# Controller-Board_Rack-PDU_1_0.net
KiCad netlist of a schematic drawn in EAGLE
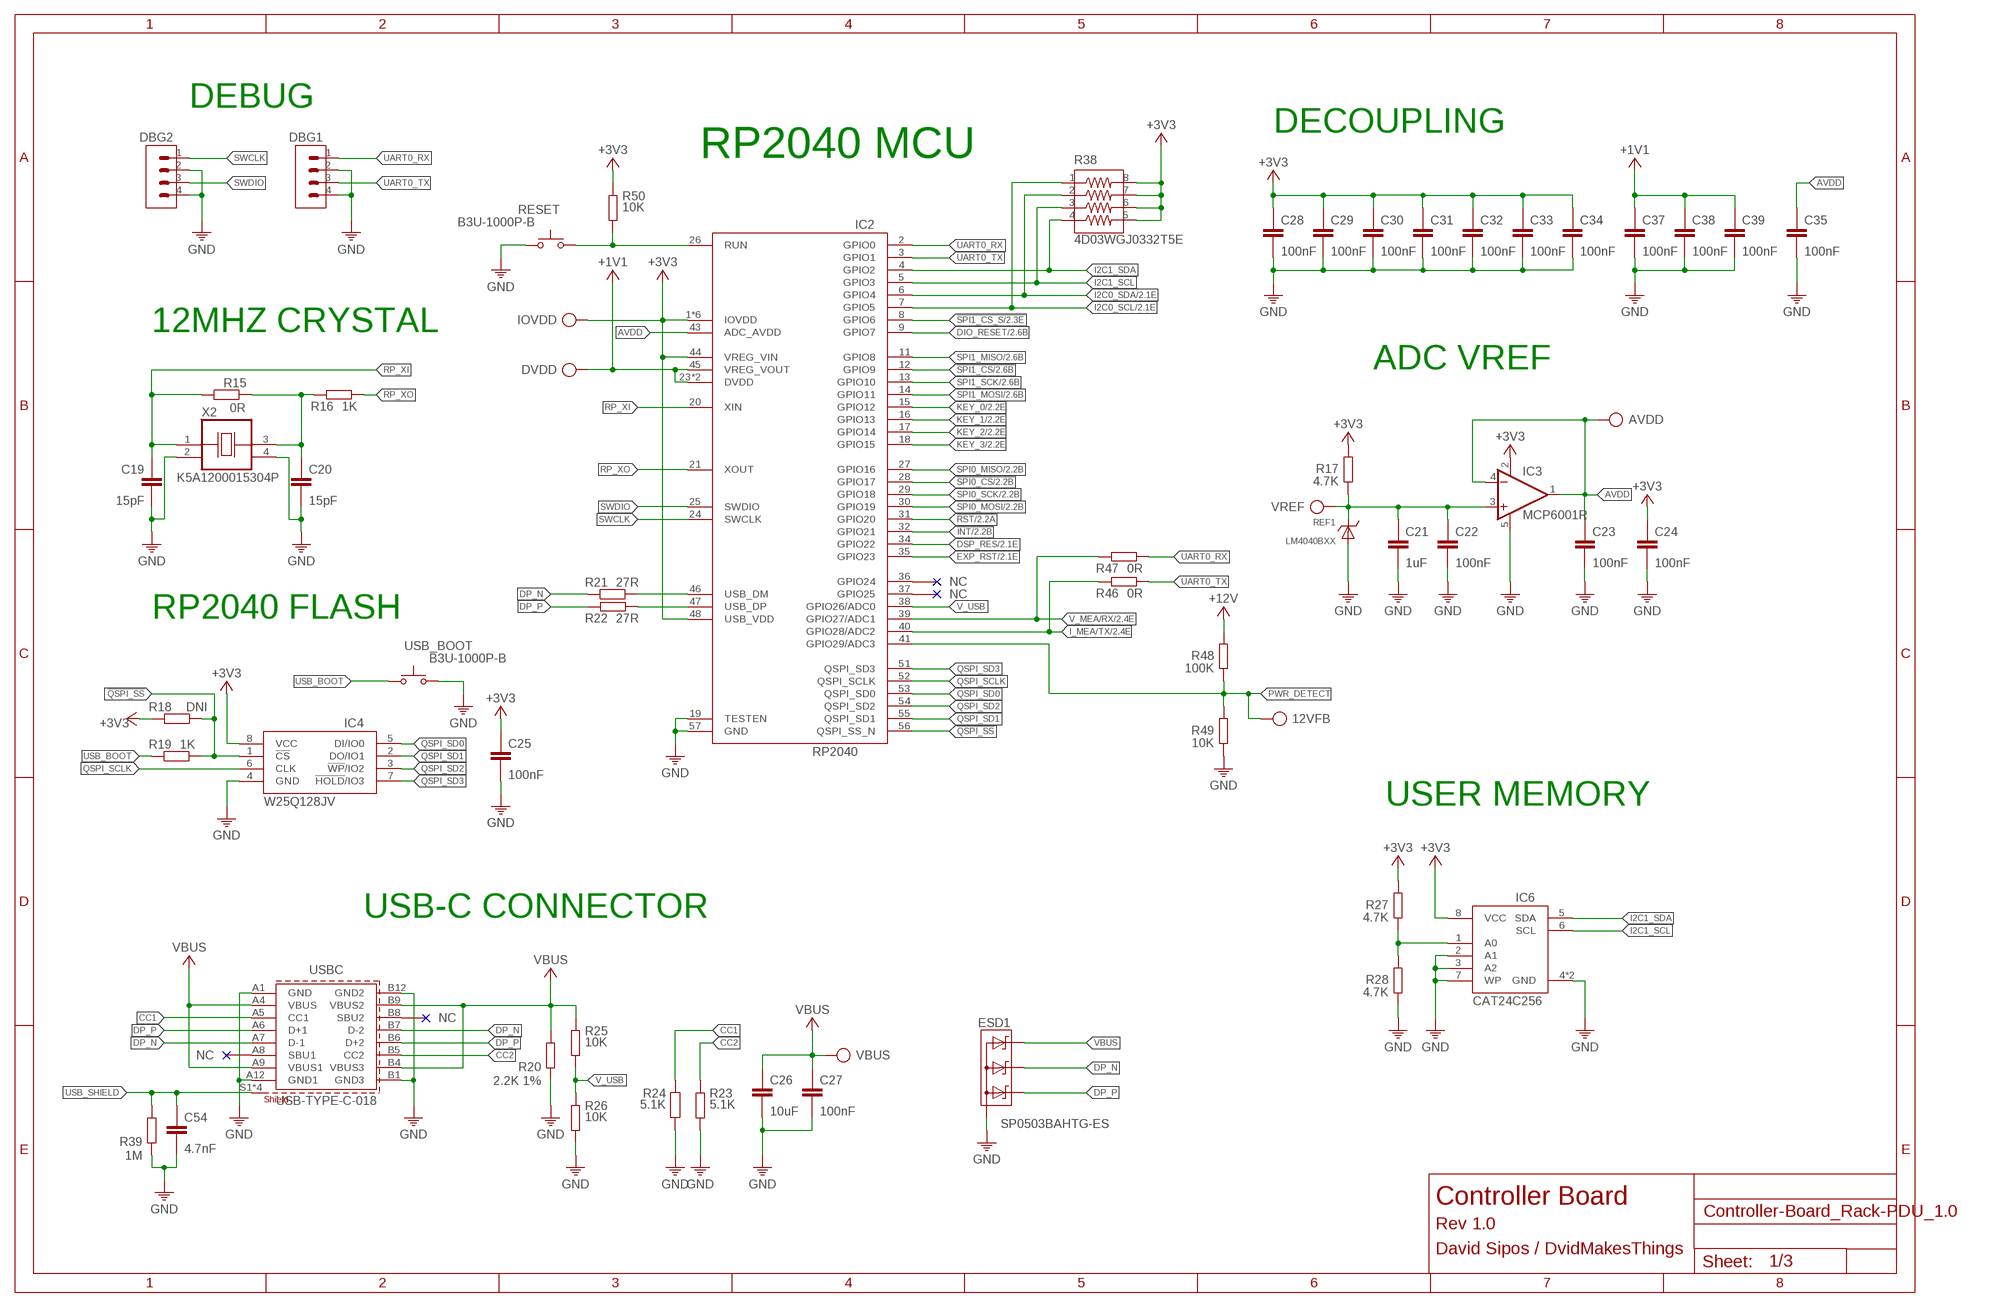
[diagram p0: schematic, sheet 1]
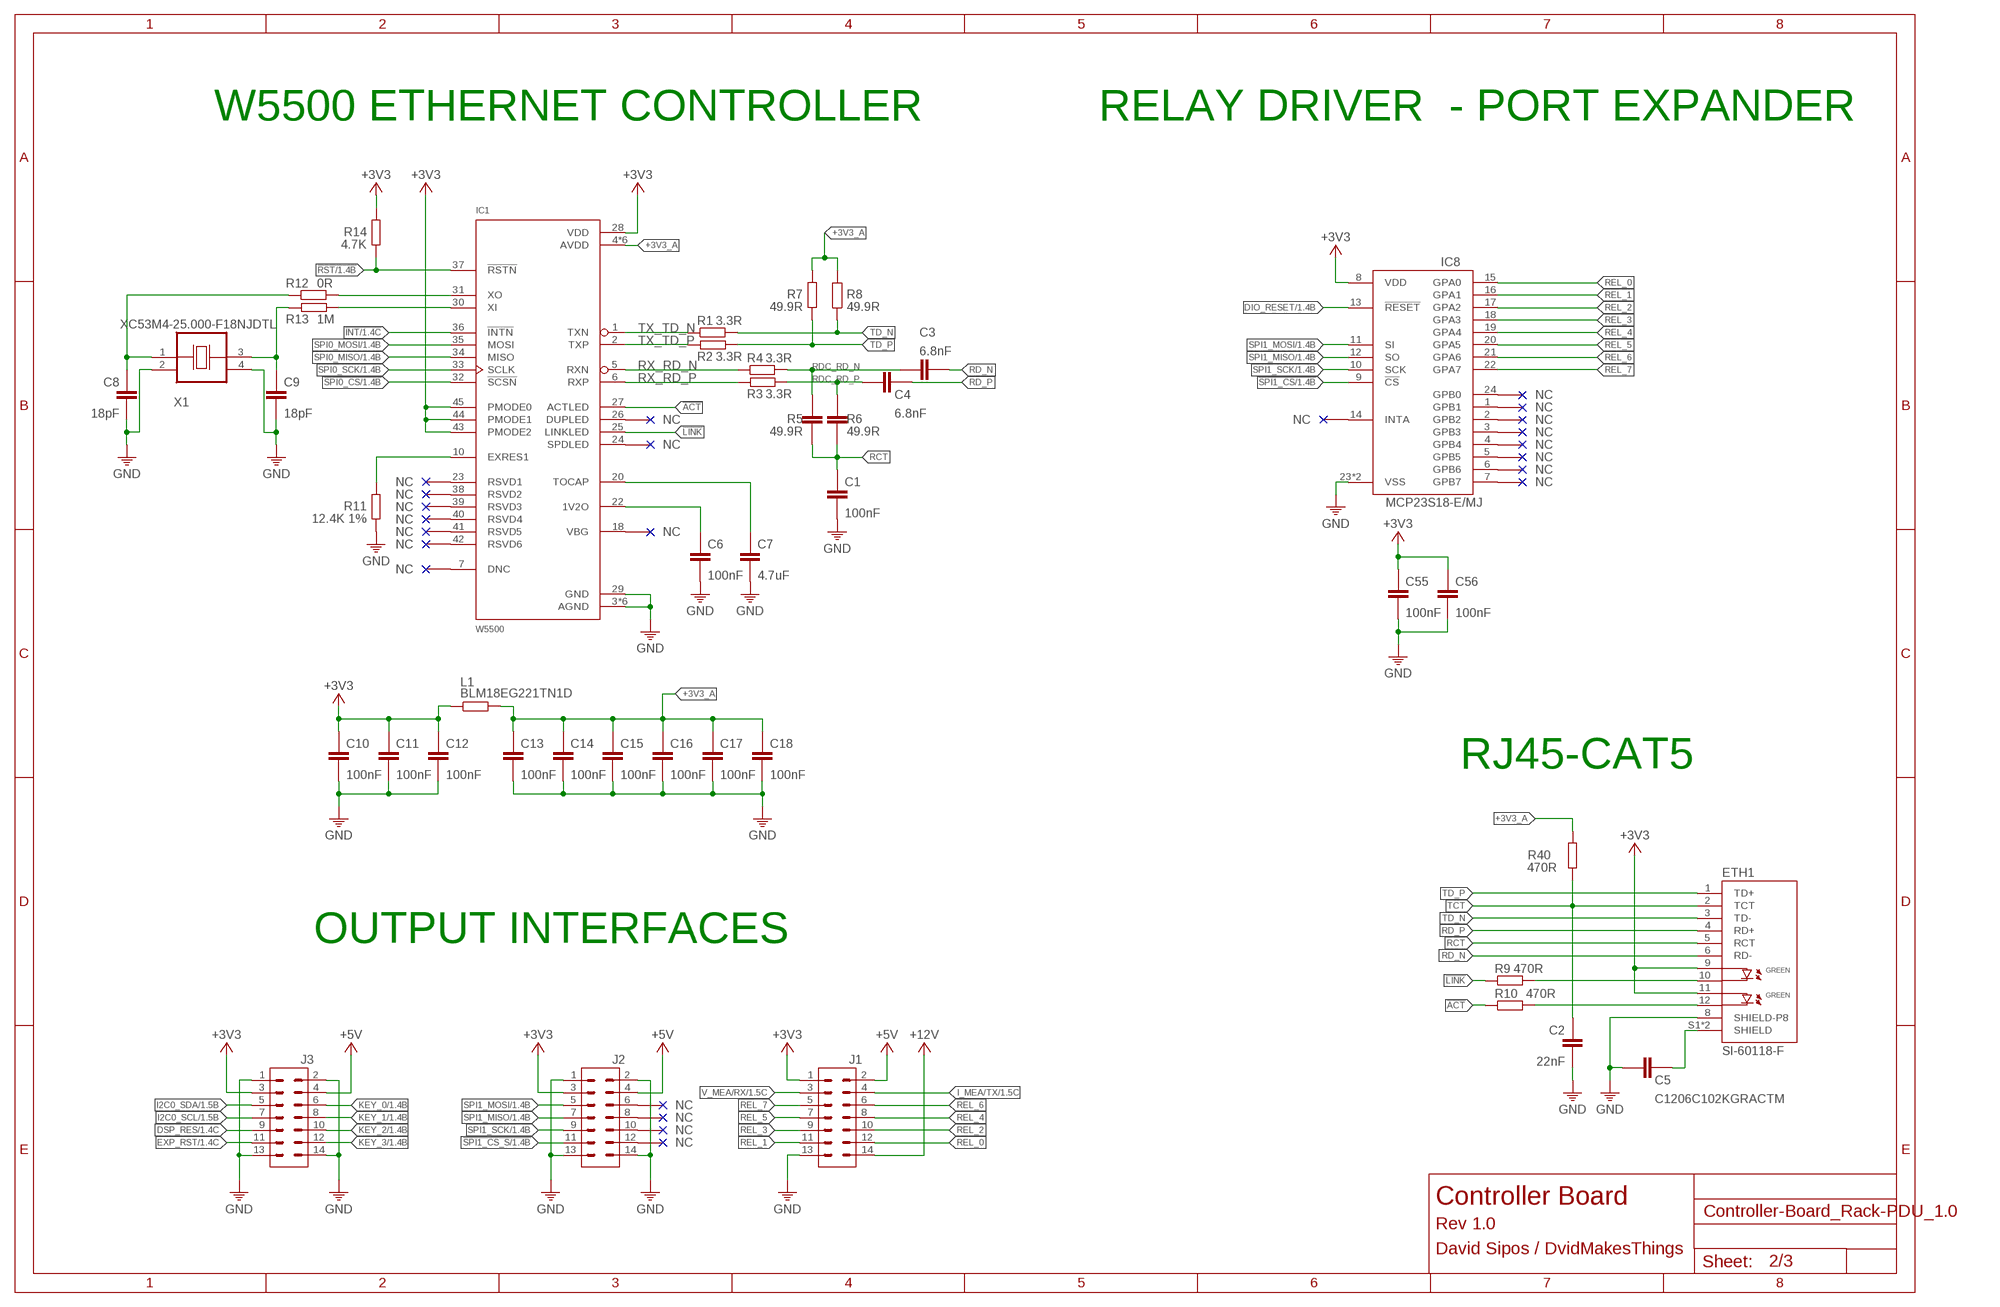
[diagram p1: schematic, sheet 2]
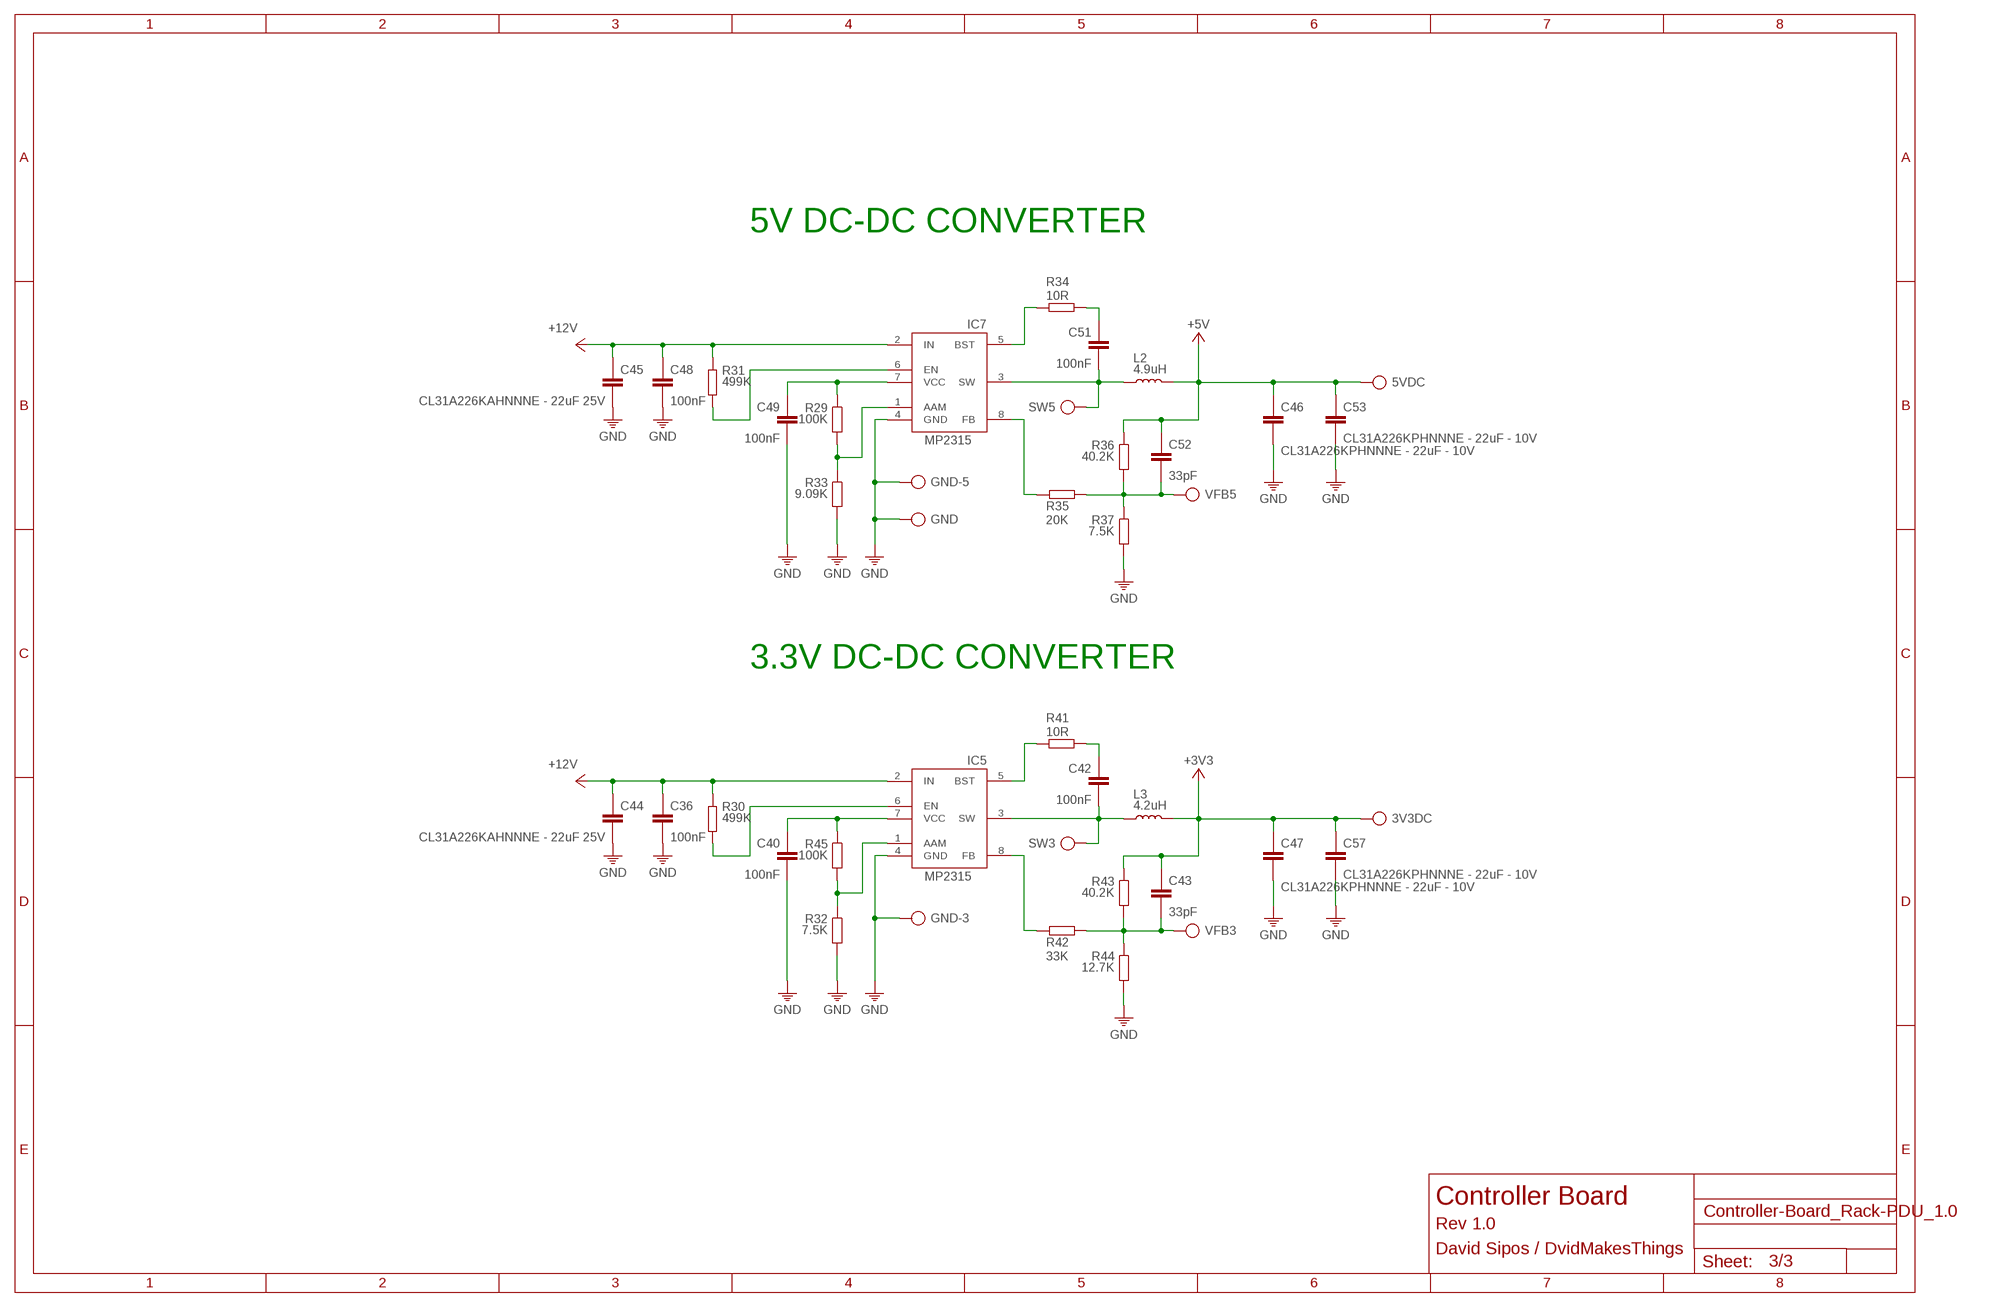
[diagram p2: schematic, sheet 3]

(export (version "E")
  (design (tool "Eeschema 10.0.6"))
  (components
    (comp (ref "12VFB")
      (value "TP")
      (footprint "eagle-import:TP")
      (libsource (lib "eagle-import") (part "TP"))
    )
    (comp (ref "AVDD")
      (value "TP")
      (footprint "eagle-import:TP")
      (libsource (lib "eagle-import") (part "TP"))
    )
    (comp (ref "C19")
      (value "15pF")
      (footprint "eagle-import:C0402")
      (libsource (lib "eagle-import") (part "C-0402"))
    )
    (comp (ref "C20")
      (value "15pF")
      (footprint "eagle-import:C0402")
      (libsource (lib "eagle-import") (part "C-0402"))
    )
    (comp (ref "C21")
      (value "1uF")
      (footprint "eagle-import:C0402")
      (libsource (lib "eagle-import") (part "C-0402"))
    )
    (comp (ref "C22")
      (value "100nF")
      (footprint "eagle-import:C0402")
      (libsource (lib "eagle-import") (part "C-0402"))
    )
    (comp (ref "C23")
      (value "100nF")
      (footprint "eagle-import:C0402")
      (libsource (lib "eagle-import") (part "C-0402"))
    )
    (comp (ref "C24")
      (value "100nF")
      (footprint "eagle-import:C0402")
      (libsource (lib "eagle-import") (part "C-0402"))
    )
    (comp (ref "C25")
      (value "100nF")
      (footprint "eagle-import:C0402")
      (libsource (lib "eagle-import") (part "C-0402"))
    )
    (comp (ref "C26")
      (value "10uF")
      (footprint "eagle-import:0805")
      (libsource (lib "eagle-import") (part "C0805"))
    )
    (comp (ref "C27")
      (value "100nF")
      (footprint "eagle-import:0402")
      (libsource (lib "eagle-import") (part "C0402"))
    )
    (comp (ref "C28")
      (value "100nF")
      (footprint "eagle-import:C0402")
      (libsource (lib "eagle-import") (part "C-0402"))
    )
    (comp (ref "C29")
      (value "100nF")
      (footprint "eagle-import:C0402")
      (libsource (lib "eagle-import") (part "C-0402"))
    )
    (comp (ref "C30")
      (value "100nF")
      (footprint "eagle-import:C0402")
      (libsource (lib "eagle-import") (part "C-0402"))
    )
    (comp (ref "C31")
      (value "100nF")
      (footprint "eagle-import:C0402")
      (libsource (lib "eagle-import") (part "C-0402"))
    )
    (comp (ref "C32")
      (value "100nF")
      (footprint "eagle-import:C0402")
      (libsource (lib "eagle-import") (part "C-0402"))
    )
    (comp (ref "C33")
      (value "100nF")
      (footprint "eagle-import:C0402")
      (libsource (lib "eagle-import") (part "C-0402"))
    )
    (comp (ref "C34")
      (value "100nF")
      (footprint "eagle-import:C0402")
      (libsource (lib "eagle-import") (part "C-0402"))
    )
    (comp (ref "C35")
      (value "100nF")
      (footprint "eagle-import:C0402")
      (libsource (lib "eagle-import") (part "C-0402"))
    )
    (comp (ref "C37")
      (value "100nF")
      (footprint "eagle-import:C0402")
      (libsource (lib "eagle-import") (part "C-0402"))
    )
    (comp (ref "C38")
      (value "100nF")
      (footprint "eagle-import:C0402")
      (libsource (lib "eagle-import") (part "C-0402"))
    )
    (comp (ref "C39")
      (value "100nF")
      (footprint "eagle-import:C0402")
      (libsource (lib "eagle-import") (part "C-0402"))
    )
    (comp (ref "C54")
      (value "4.7nF")
      (footprint "eagle-import:0402")
      (libsource (lib "eagle-import") (part "C0402"))
    )
    (comp (ref "DBG1")
      (value "CON-1X4")
      (footprint "eagle-import:1X4")
      (libsource (lib "eagle-import") (part "CON-1X4"))
    )
    (comp (ref "DBG2")
      (value "CON-1X4")
      (footprint "eagle-import:1X4")
      (libsource (lib "eagle-import") (part "CON-1X4"))
    )
    (comp (ref "DVDD")
      (value "TP")
      (footprint "eagle-import:TP")
      (libsource (lib "eagle-import") (part "TP"))
    )
    (comp (ref "ESD1")
      (value "SP0503BAHTG-ES")
      (footprint "eagle-import:SOT143")
      (libsource (lib "eagle-import") (part "SP0503BAHT"))
    )
    (comp (ref "IC2")
      (value "RP2040")
      (footprint "eagle-import:QFN40P700X700X100-57T510")
      (libsource (lib "eagle-import") (part "RP2040"))
    )
    (comp (ref "IC3")
      (value "MCP6001R")
      (footprint "eagle-import:SOT23-5")
      (libsource (lib "eagle-import") (part "MCP6001RT"))
    )
    (comp (ref "IC4")
      (value "W25Q128JVPIQ")
      (footprint "eagle-import:SON127P600X500X75-8N")
      (libsource (lib "eagle-import") (part "W25Q128JVP"))
    )
    (comp (ref "IC6")
      (value "CAT24C256HU4IGT3")
      (footprint "eagle-import:SON50P300X200X50-9T130X140N")
      (libsource (lib "eagle-import") (part "CAT24C256-HU4"))
    )
    (comp (ref "IOVDD")
      (value "TP")
      (footprint "eagle-import:TP")
      (libsource (lib "eagle-import") (part "TP"))
    )
    (comp (ref "R15")
      (value "0R")
      (footprint "eagle-import:0402")
      (libsource (lib "eagle-import") (part "R0402"))
    )
    (comp (ref "R16")
      (value "1K")
      (footprint "eagle-import:0402")
      (libsource (lib "eagle-import") (part "R0402"))
    )
    (comp (ref "R17")
      (value "4.7K")
      (footprint "eagle-import:0402")
      (libsource (lib "eagle-import") (part "R0402"))
    )
    (comp (ref "R18")
      (value "DNI")
      (footprint "eagle-import:0402")
      (libsource (lib "eagle-import") (part "R0402"))
    )
    (comp (ref "R19")
      (value "1K")
      (footprint "eagle-import:0402")
      (libsource (lib "eagle-import") (part "R0402"))
    )
    (comp (ref "R20")
      (value "2.2K 1%")
      (footprint "eagle-import:0402")
      (libsource (lib "eagle-import") (part "ds_passive_46685041_R0402"))
    )
    (comp (ref "R21")
      (value "27R")
      (footprint "eagle-import:0402")
      (libsource (lib "eagle-import") (part "R0402"))
    )
    (comp (ref "R22")
      (value "27R")
      (footprint "eagle-import:0402")
      (libsource (lib "eagle-import") (part "R0402"))
    )
    (comp (ref "R23")
      (value "5.1K")
      (footprint "eagle-import:0402")
      (libsource (lib "eagle-import") (part "ds_passive_46685041_R0402"))
    )
    (comp (ref "R24")
      (value "5.1K")
      (footprint "eagle-import:0402")
      (libsource (lib "eagle-import") (part "ds_passive_46685041_R0402"))
    )
    (comp (ref "R25")
      (value "10K")
      (footprint "eagle-import:0402")
      (libsource (lib "eagle-import") (part "ds_passive_46685041_R0402"))
    )
    (comp (ref "R26")
      (value "10K")
      (footprint "eagle-import:0402")
      (libsource (lib "eagle-import") (part "ds_passive_46685041_R0402"))
    )
    (comp (ref "R27")
      (value "4.7K")
      (footprint "eagle-import:0402")
      (libsource (lib "eagle-import") (part "R0402"))
    )
    (comp (ref "R28")
      (value "4.7K")
      (footprint "eagle-import:0402")
      (libsource (lib "eagle-import") (part "R0402"))
    )
    (comp (ref "R38")
      (value "4D03WGJ0332T5E")
      (footprint "eagle-import:742C083103JP")
      (fields
        (field (name "MANUFACTURER") "CTS Resistor Products")
        (field (name "MPN") "742C083103JP")
        (field (name "CREATED_BY") "PCBLayout.com")
      )
      (libsource (lib "eagle-import") (part "742C083103JP"))
    )
    (comp (ref "R39")
      (value "1M")
      (footprint "eagle-import:0402")
      (libsource (lib "eagle-import") (part "ds_passive_46685041_R0402"))
    )
    (comp (ref "R46")
      (value "0R")
      (footprint "eagle-import:0402")
      (libsource (lib "eagle-import") (part "R0402"))
    )
    (comp (ref "R47")
      (value "0R")
      (footprint "eagle-import:0402")
      (libsource (lib "eagle-import") (part "R0402"))
    )
    (comp (ref "R48")
      (value "100K")
      (footprint "eagle-import:0402")
      (libsource (lib "eagle-import") (part "R0402"))
    )
    (comp (ref "R49")
      (value "10K")
      (footprint "eagle-import:0402")
      (libsource (lib "eagle-import") (part "R0402"))
    )
    (comp (ref "R50")
      (value "10K")
      (footprint "eagle-import:0402")
      (libsource (lib "eagle-import") (part "ds_passive_46685041_R0402"))
    )
    (comp (ref "REF1")
      (value "LM4040BXX")
      (footprint "eagle-import:SOT23")
      (libsource (lib "eagle-import") (part "LM4040BXX"))
    )
    (comp (ref "RESET")
      (value "B3U-1000P-B")
      (footprint "eagle-import:SWITCH-OMRON_B3U-1000P")
      (libsource (lib "eagle-import") (part "SWITCH-OMRON_B3U-1000P"))
    )
    (comp (ref "USBC")
      (value "USB-TYPE-C-018")
      (footprint "eagle-import:629722000214")
      (libsource (lib "eagle-import") (part "629722000214"))
    )
    (comp (ref "USB_BOOT")
      (value "B3U-1000P-B")
      (footprint "eagle-import:SWITCH-OMRON_B3U-1000P")
      (libsource (lib "eagle-import") (part "SWITCH-OMRON_B3U-1000P"))
    )
    (comp (ref "VBUS")
      (value "TP")
      (footprint "eagle-import:TP")
      (libsource (lib "eagle-import") (part "TP"))
    )
    (comp (ref "VREF")
      (value "TP")
      (footprint "eagle-import:TP")
      (libsource (lib "eagle-import") (part "TP"))
    )
    (comp (ref "X2")
      (value "K5A1200015304P")
      (footprint "eagle-import:OSCCC500X320X130")
      (libsource (lib "eagle-import") (part "CRYSTAL"))
    )
    (comp (ref "C1")
      (value "100nF")
      (footprint "eagle-import:C0402")
      (libsource (lib "eagle-import") (part "C-0402"))
    )
    (comp (ref "C2")
      (value "22nF")
      (footprint "eagle-import:C0402")
      (libsource (lib "eagle-import") (part "C-0402"))
    )
    (comp (ref "C3")
      (value "6.8nF")
      (footprint "eagle-import:C0402")
      (libsource (lib "eagle-import") (part "C-0402"))
    )
    (comp (ref "C4")
      (value "6.8nF")
      (footprint "eagle-import:C0402")
      (libsource (lib "eagle-import") (part "C-0402"))
    )
    (comp (ref "C5")
      (value "C1206C102KGRACTM")
      (footprint "eagle-import:C1206")
      (libsource (lib "eagle-import") (part "C-1206"))
    )
    (comp (ref "C6")
      (value "100nF")
      (footprint "eagle-import:C0402")
      (libsource (lib "eagle-import") (part "C-0402"))
    )
    (comp (ref "C7")
      (value "4.7uF")
      (footprint "eagle-import:C0402")
      (libsource (lib "eagle-import") (part "C-0402"))
    )
    (comp (ref "C8")
      (value "18pF")
      (footprint "eagle-import:C0402")
      (libsource (lib "eagle-import") (part "C-0402"))
    )
    (comp (ref "C9")
      (value "18pF")
      (footprint "eagle-import:C0402")
      (libsource (lib "eagle-import") (part "C-0402"))
    )
    (comp (ref "C10")
      (value "100nF")
      (footprint "eagle-import:C0402")
      (libsource (lib "eagle-import") (part "C-0402"))
    )
    (comp (ref "C11")
      (value "100nF")
      (footprint "eagle-import:C0402")
      (libsource (lib "eagle-import") (part "C-0402"))
    )
    (comp (ref "C12")
      (value "100nF")
      (footprint "eagle-import:C0402")
      (libsource (lib "eagle-import") (part "C-0402"))
    )
    (comp (ref "C13")
      (value "100nF")
      (footprint "eagle-import:C0402")
      (libsource (lib "eagle-import") (part "C-0402"))
    )
    (comp (ref "C14")
      (value "100nF")
      (footprint "eagle-import:C0402")
      (libsource (lib "eagle-import") (part "C-0402"))
    )
    (comp (ref "C15")
      (value "100nF")
      (footprint "eagle-import:C0402")
      (libsource (lib "eagle-import") (part "C-0402"))
    )
    (comp (ref "C16")
      (value "100nF")
      (footprint "eagle-import:C0402")
      (libsource (lib "eagle-import") (part "C-0402"))
    )
    (comp (ref "C17")
      (value "100nF")
      (footprint "eagle-import:C0402")
      (libsource (lib "eagle-import") (part "C-0402"))
    )
    (comp (ref "C18")
      (value "100nF")
      (footprint "eagle-import:C0402")
      (libsource (lib "eagle-import") (part "C-0402"))
    )
    (comp (ref "C55")
      (value "100nF")
      (footprint "eagle-import:C0402")
      (libsource (lib "eagle-import") (part "C-0402"))
    )
    (comp (ref "C56")
      (value "100nF")
      (footprint "eagle-import:C0402")
      (libsource (lib "eagle-import") (part "C-0402"))
    )
    (comp (ref "ETH1")
      (value "SI-60118-F")
      (footprint "eagle-import:RJ45-CAT5")
      (fields (field (name "MANUFACTURER") "Bel Fuse"))
      (libsource (lib "eagle-import") (part "RJ45-CAT5"))
    )
    (comp (ref "IC1")
      (value "W5500")
      (footprint "eagle-import:LQFP48")
      (libsource (lib "eagle-import") (part "W5500"))
    )
    (comp (ref "IC8")
      (value "MCP23S18-E/MJ")
      (footprint "eagle-import:QFN50P400X400X100-25T265")
      (libsource (lib "eagle-import") (part "MCP23S18"))
    )
    (comp (ref "J1")
      (value "CON-2X7")
      (footprint "eagle-import:2X7")
      (libsource (lib "eagle-import") (part "CON-2X7"))
    )
    (comp (ref "J2")
      (value "CON-2X7")
      (footprint "eagle-import:2X7")
      (libsource (lib "eagle-import") (part "CON-2X7"))
    )
    (comp (ref "J3")
      (value "CON-2X7")
      (footprint "eagle-import:2X7")
      (libsource (lib "eagle-import") (part "CON-2X7"))
    )
    (comp (ref "L1")
      (value "BLM18EG221TN1D")
      (footprint "eagle-import:0603")
      (libsource (lib "eagle-import") (part "R0603"))
    )
    (comp (ref "R1")
      (value "3.3R")
      (footprint "eagle-import:0402")
      (libsource (lib "eagle-import") (part "R0402"))
    )
    (comp (ref "R2")
      (value "3.3R")
      (footprint "eagle-import:0402")
      (libsource (lib "eagle-import") (part "R0402"))
    )
    (comp (ref "R3")
      (value "3.3R")
      (footprint "eagle-import:0402")
      (libsource (lib "eagle-import") (part "R0402"))
    )
    (comp (ref "R4")
      (value "3.3R")
      (footprint "eagle-import:0402")
      (libsource (lib "eagle-import") (part "R0402"))
    )
    (comp (ref "R5")
      (value "49.9R")
      (footprint "eagle-import:C0402")
      (libsource (lib "eagle-import") (part "C-0402"))
    )
    (comp (ref "R6")
      (value "49.9R")
      (footprint "eagle-import:C0402")
      (libsource (lib "eagle-import") (part "C-0402"))
    )
    (comp (ref "R7")
      (value "49.9R")
      (footprint "eagle-import:0402")
      (libsource (lib "eagle-import") (part "R0402"))
    )
    (comp (ref "R8")
      (value "49.9R")
      (footprint "eagle-import:0402")
      (libsource (lib "eagle-import") (part "R0402"))
    )
    (comp (ref "R9")
      (value "470R")
      (footprint "eagle-import:0402")
      (libsource (lib "eagle-import") (part "R0402"))
    )
    (comp (ref "R10")
      (value "470R")
      (footprint "eagle-import:0402")
      (libsource (lib "eagle-import") (part "R0402"))
    )
    (comp (ref "R11")
      (value "12.4K 1%")
      (footprint "eagle-import:0402")
      (libsource (lib "eagle-import") (part "R0402"))
    )
    (comp (ref "R12")
      (value "0R")
      (footprint "eagle-import:0402")
      (libsource (lib "eagle-import") (part "R0402"))
    )
    (comp (ref "R13")
      (value "1M")
      (footprint "eagle-import:0402")
      (libsource (lib "eagle-import") (part "R0402"))
    )
    (comp (ref "R14")
      (value "4.7K")
      (footprint "eagle-import:0402")
      (libsource (lib "eagle-import") (part "R0402"))
    )
    (comp (ref "R40")
      (value "470R")
      (footprint "eagle-import:0402")
      (libsource (lib "eagle-import") (part "R0402"))
    )
    (comp (ref "X1")
      (value "XC53M4-25.000-F18NJDTL")
      (footprint "eagle-import:OSCCC500X320X130")
      (libsource (lib "eagle-import") (part "CRYSTAL"))
    )
    (comp (ref "3V3DC")
      (value "TP")
      (footprint "eagle-import:TP")
      (libsource (lib "eagle-import") (part "TP"))
    )
    (comp (ref "5VDC")
      (value "TP")
      (footprint "eagle-import:TP")
      (libsource (lib "eagle-import") (part "TP"))
    )
    (comp (ref "C36")
      (value "100nF")
      (footprint "eagle-import:0402")
      (libsource (lib "eagle-import") (part "C0402"))
    )
    (comp (ref "C40")
      (value "100nF")
      (footprint "eagle-import:0402")
      (libsource (lib "eagle-import") (part "C0402"))
    )
    (comp (ref "C42")
      (value "100nF")
      (footprint "eagle-import:0402")
      (libsource (lib "eagle-import") (part "C0402"))
    )
    (comp (ref "C43")
      (value "33pF")
      (footprint "eagle-import:0402")
      (libsource (lib "eagle-import") (part "C0402"))
    )
    (comp (ref "C44")
      (value "CL31A226KAHNNNE - 22uF 25V")
      (footprint "eagle-import:C1206")
      (libsource (lib "eagle-import") (part "C-1206"))
    )
    (comp (ref "C45")
      (value "CL31A226KAHNNNE - 22uF 25V")
      (footprint "eagle-import:C1206")
      (libsource (lib "eagle-import") (part "C-1206"))
    )
    (comp (ref "C46")
      (value "CL31A226KPHNNNE - 22uF - 10V")
      (footprint "eagle-import:C1206")
      (libsource (lib "eagle-import") (part "C-1206"))
    )
    (comp (ref "C47")
      (value "CL31A226KPHNNNE - 22uF - 10V")
      (footprint "eagle-import:C1206")
      (libsource (lib "eagle-import") (part "C-1206"))
    )
    (comp (ref "C48")
      (value "100nF")
      (footprint "eagle-import:0402")
      (libsource (lib "eagle-import") (part "C0402"))
    )
    (comp (ref "C49")
      (value "100nF")
      (footprint "eagle-import:0402")
      (libsource (lib "eagle-import") (part "C0402"))
    )
    (comp (ref "C51")
      (value "100nF")
      (footprint "eagle-import:0402")
      (libsource (lib "eagle-import") (part "C0402"))
    )
    (comp (ref "C52")
      (value "33pF")
      (footprint "eagle-import:0402")
      (libsource (lib "eagle-import") (part "C0402"))
    )
    (comp (ref "C53")
      (value "CL31A226KPHNNNE - 22uF - 10V")
      (footprint "eagle-import:C1206")
      (libsource (lib "eagle-import") (part "C-1206"))
    )
    (comp (ref "C57")
      (value "CL31A226KPHNNNE - 22uF - 10V")
      (footprint "eagle-import:C1206")
      (libsource (lib "eagle-import") (part "C-1206"))
    )
    (comp (ref "GND") (value "TP") (footprint "eagle-import:TP") (libsource (lib "eagle-import") (part "TP")))
    (comp (ref "GND-3")
      (value "TP")
      (footprint "eagle-import:TP")
      (libsource (lib "eagle-import") (part "TP"))
    )
    (comp (ref "GND-5")
      (value "TP")
      (footprint "eagle-import:TP")
      (libsource (lib "eagle-import") (part "TP"))
    )
    (comp (ref "IC5")
      (value "MP2315S")
      (footprint "eagle-import:SOT65P280X110-8N")
      (libsource (lib "eagle-import") (part "MP2315TSOT23-8"))
    )
    (comp (ref "IC7")
      (value "MP2315GJ-Z")
      (footprint "eagle-import:SOT65P280X110-8N")
      (libsource (lib "eagle-import") (part "MP2315TSOT23-8"))
    )
    (comp (ref "L2")
      (value "4.9uH")
      (footprint "eagle-import:SRR5228A")
      (libsource (lib "eagle-import") (part "L"))
    )
    (comp (ref "L3")
      (value "4.2uH")
      (footprint "eagle-import:SRR5228A")
      (libsource (lib "eagle-import") (part "L"))
    )
    (comp (ref "R29")
      (value "100K")
      (footprint "eagle-import:0402")
      (libsource (lib "eagle-import") (part "R0402"))
    )
    (comp (ref "R30")
      (value "499K")
      (footprint "eagle-import:0402")
      (libsource (lib "eagle-import") (part "R0402"))
    )
    (comp (ref "R31")
      (value "499K")
      (footprint "eagle-import:0402")
      (libsource (lib "eagle-import") (part "R0402"))
    )
    (comp (ref "R32")
      (value "7.5K")
      (footprint "eagle-import:0402")
      (libsource (lib "eagle-import") (part "R0402"))
    )
    (comp (ref "R33")
      (value "9.09K")
      (footprint "eagle-import:0402")
      (libsource (lib "eagle-import") (part "R0402"))
    )
    (comp (ref "R34")
      (value "10R")
      (footprint "eagle-import:0402")
      (libsource (lib "eagle-import") (part "R0402"))
    )
    (comp (ref "R35")
      (value "20K")
      (footprint "eagle-import:0402")
      (libsource (lib "eagle-import") (part "R0402"))
    )
    (comp (ref "R36")
      (value "40.2K")
      (footprint "eagle-import:0402")
      (libsource (lib "eagle-import") (part "R0402"))
    )
    (comp (ref "R37")
      (value "7.5K")
      (footprint "eagle-import:0402")
      (libsource (lib "eagle-import") (part "R0402"))
    )
    (comp (ref "R41")
      (value "10R")
      (footprint "eagle-import:0402")
      (libsource (lib "eagle-import") (part "R0402"))
    )
    (comp (ref "R42")
      (value "33K")
      (footprint "eagle-import:0402")
      (libsource (lib "eagle-import") (part "R0402"))
    )
    (comp (ref "R43")
      (value "40.2K")
      (footprint "eagle-import:0402")
      (libsource (lib "eagle-import") (part "R0402"))
    )
    (comp (ref "R44")
      (value "12.7K")
      (footprint "eagle-import:0402")
      (libsource (lib "eagle-import") (part "R0402"))
    )
    (comp (ref "R45")
      (value "100K")
      (footprint "eagle-import:0402")
      (libsource (lib "eagle-import") (part "R0402"))
    )
    (comp (ref "SW3") (value "TP") (footprint "eagle-import:TP") (libsource (lib "eagle-import") (part "TP")))
    (comp (ref "SW5") (value "TP") (footprint "eagle-import:TP") (libsource (lib "eagle-import") (part "TP")))
    (comp (ref "VFB3")
      (value "TP")
      (footprint "eagle-import:TP")
      (libsource (lib "eagle-import") (part "TP"))
    )
    (comp (ref "VFB5")
      (value "TP")
      (footprint "eagle-import:TP")
      (libsource (lib "eagle-import") (part "TP"))
    )
  )
  (nets
    (net (code "1") (name "+1V1") (class "Default")
      (node (ref "C37") (pin "1") (pinfunction "1_1") (pintype "passive"))
      (node (ref "C38") (pin "1") (pinfunction "1_1") (pintype "passive"))
      (node (ref "C39") (pin "1") (pinfunction "1_1") (pintype "passive"))
      (node (ref "DVDD") (pin "TP") (pinfunction "P$1_TP") (pintype "bidirectional"))
      (node (ref "IC2") (pin "23") (pinfunction "DVDD_23") (pintype "bidirectional"))
      (node (ref "IC2") (pin "45") (pinfunction "VREG_VOUT_45") (pintype "bidirectional"))
      (node (ref "IC2") (pin "50") (pinfunction "DVDD_50") (pintype "bidirectional"))
    )
    (net (code "2") (name "+3V3") (class "Default")
      (node (ref "3V3DC") (pin "TP") (pinfunction "P$1_TP") (pintype "bidirectional"))
      (node (ref "C10") (pin "1") (pinfunction "1_1") (pintype "passive"))
      (node (ref "C11") (pin "1") (pinfunction "1_1") (pintype "passive"))
      (node (ref "C12") (pin "1") (pinfunction "1_1") (pintype "passive"))
      (node (ref "C24") (pin "1") (pinfunction "1_1") (pintype "passive"))
      (node (ref "C25") (pin "1") (pinfunction "1_1") (pintype "passive"))
      (node (ref "C28") (pin "1") (pinfunction "1_1") (pintype "passive"))
      (node (ref "C29") (pin "1") (pinfunction "1_1") (pintype "passive"))
      (node (ref "C30") (pin "1") (pinfunction "1_1") (pintype "passive"))
      (node (ref "C31") (pin "1") (pinfunction "1_1") (pintype "passive"))
      (node (ref "C32") (pin "1") (pinfunction "1_1") (pintype "passive"))
      (node (ref "C33") (pin "1") (pinfunction "1_1") (pintype "passive"))
      (node (ref "C34") (pin "1") (pinfunction "1_1") (pintype "passive"))
      (node (ref "C43") (pin "1") (pinfunction "1_1") (pintype "passive"))
      (node (ref "C47") (pin "1") (pinfunction "1_1") (pintype "passive"))
      (node (ref "C55") (pin "1") (pinfunction "1_1") (pintype "passive"))
      (node (ref "C56") (pin "1") (pinfunction "1_1") (pintype "passive"))
      (node (ref "C57") (pin "1") (pinfunction "1_1") (pintype "passive"))
      (node (ref "ETH1") (pin "11") (pinfunction "GA2_11") (pintype "passive"))
      (node (ref "ETH1") (pin "9") (pinfunction "GA1_9") (pintype "passive"))
      (node (ref "IC1") (pin "28") (pinfunction "VDD_28") (pintype "power_in"))
      (node (ref "IC1") (pin "43") (pinfunction "PMODE2_43") (pintype "input"))
      (node (ref "IC1") (pin "44") (pinfunction "PMODE1_44") (pintype "input"))
      (node (ref "IC1") (pin "45") (pinfunction "PMODE0_45") (pintype "input"))
      (node (ref "IC2") (pin "1") (pinfunction "IOVDD_1") (pintype "bidirectional"))
      (node (ref "IC2") (pin "10") (pinfunction "IOVDD_10") (pintype "bidirectional"))
      (node (ref "IC2") (pin "22") (pinfunction "IOVDD_22") (pintype "bidirectional"))
      (node (ref "IC2") (pin "33") (pinfunction "IOVDD_33") (pintype "bidirectional"))
      (node (ref "IC2") (pin "42") (pinfunction "IOVDD_42") (pintype "bidirectional"))
      (node (ref "IC2") (pin "44") (pinfunction "VREG_VIN_44") (pintype "bidirectional"))
      (node (ref "IC2") (pin "48") (pinfunction "USB_VDD_48") (pintype "bidirectional"))
      (node (ref "IC2") (pin "49") (pinfunction "IOVDD_49") (pintype "bidirectional"))
      (node (ref "IC3") (pin "2") (pinfunction "V+_2") (pintype "power_in"))
      (node (ref "IC4") (pin "8") (pinfunction "VCC_8") (pintype "power_in"))
      (node (ref "IC6") (pin "8") (pinfunction "VCC_8") (pintype "power_in"))
      (node (ref "IC8") (pin "8") (pinfunction "VDD_8") (pintype "power_in"))
      (node (ref "IOVDD") (pin "TP") (pinfunction "P$1_TP") (pintype "bidirectional"))
      (node (ref "J1") (pin "1") (pinfunction "1_1") (pintype "bidirectional"))
      (node (ref "J2") (pin "3") (pinfunction "3_3") (pintype "bidirectional"))
      (node (ref "J3") (pin "3") (pinfunction "3_3") (pintype "bidirectional"))
      (node (ref "L1") (pin "1") (pinfunction "1_1") (pintype "passive"))
      (node (ref "L3") (pin "2") (pinfunction "2_2") (pintype "passive"))
      (node (ref "R14") (pin "2") (pinfunction "2_2") (pintype "passive"))
      (node (ref "R17") (pin "2") (pinfunction "2_2") (pintype "passive"))
      (node (ref "R18") (pin "2") (pinfunction "2_2") (pintype "passive"))
      (node (ref "R27") (pin "2") (pinfunction "2_2") (pintype "passive"))
      (node (ref "R38") (pin "5") (pinfunction "5_5") (pintype "passive"))
      (node (ref "R38") (pin "6") (pinfunction "6_6") (pintype "passive"))
      (node (ref "R38") (pin "7") (pinfunction "7_7") (pintype "passive"))
      (node (ref "R38") (pin "8") (pinfunction "8_8") (pintype "passive"))
      (node (ref "R43") (pin "1") (pinfunction "1_1") (pintype "passive"))
      (node (ref "R50") (pin "1") (pinfunction "1_1") (pintype "passive"))
    )
    (net (code "3") (name "+3V3_A") (class "Default")
      (node (ref "C13") (pin "1") (pinfunction "1_1") (pintype "passive"))
      (node (ref "C14") (pin "1") (pinfunction "1_1") (pintype "passive"))
      (node (ref "C15") (pin "1") (pinfunction "1_1") (pintype "passive"))
      (node (ref "C16") (pin "1") (pinfunction "1_1") (pintype "passive"))
      (node (ref "C17") (pin "1") (pinfunction "1_1") (pintype "passive"))
      (node (ref "C18") (pin "1") (pinfunction "1_1") (pintype "passive"))
      (node (ref "IC1") (pin "11") (pinfunction "AVDD_11") (pintype "power_in"))
      (node (ref "IC1") (pin "15") (pinfunction "AVDD_15") (pintype "power_in"))
      (node (ref "IC1") (pin "17") (pinfunction "AVDD_17") (pintype "power_in"))
      (node (ref "IC1") (pin "21") (pinfunction "AVDD_21") (pintype "power_in"))
      (node (ref "IC1") (pin "4") (pinfunction "AVDD_4") (pintype "power_in"))
      (node (ref "IC1") (pin "8") (pinfunction "AVDD_8") (pintype "power_in"))
      (node (ref "L1") (pin "2") (pinfunction "2_2") (pintype "passive"))
      (node (ref "R40") (pin "2") (pinfunction "2_2") (pintype "passive"))
      (node (ref "R7") (pin "2") (pinfunction "2_2") (pintype "passive"))
      (node (ref "R8") (pin "2") (pinfunction "2_2") (pintype "passive"))
    )
    (net (code "4") (name "+5V") (class "Default")
      (node (ref "5VDC") (pin "TP") (pinfunction "P$1_TP") (pintype "bidirectional"))
      (node (ref "C46") (pin "1") (pinfunction "1_1") (pintype "passive"))
      (node (ref "C52") (pin "1") (pinfunction "1_1") (pintype "passive"))
      (node (ref "C53") (pin "1") (pinfunction "1_1") (pintype "passive"))
      (node (ref "J1") (pin "2") (pinfunction "2_2") (pintype "bidirectional"))
      (node (ref "J2") (pin "4") (pinfunction "4_4") (pintype "bidirectional"))
      (node (ref "J3") (pin "4") (pinfunction "4_4") (pintype "bidirectional"))
      (node (ref "L2") (pin "2") (pinfunction "2_2") (pintype "passive"))
      (node (ref "R36") (pin "1") (pinfunction "1_1") (pintype "passive"))
    )
    (net (code "5") (name "+12V") (class "Default")
      (node (ref "C36") (pin "1") (pinfunction "1_1") (pintype "passive"))
      (node (ref "C44") (pin "1") (pinfunction "1_1") (pintype "passive"))
      (node (ref "C45") (pin "1") (pinfunction "1_1") (pintype "passive"))
      (node (ref "C48") (pin "1") (pinfunction "1_1") (pintype "passive"))
      (node (ref "IC5") (pin "2") (pinfunction "IN_2") (pintype "bidirectional"))
      (node (ref "IC7") (pin "2") (pinfunction "IN_2") (pintype "bidirectional"))
      (node (ref "J1") (pin "14") (pinfunction "14_14") (pintype "bidirectional"))
      (node (ref "R30") (pin "1") (pinfunction "1_1") (pintype "passive"))
      (node (ref "R31") (pin "1") (pinfunction "1_1") (pintype "passive"))
      (node (ref "R48") (pin "2") (pinfunction "2_2") (pintype "passive"))
    )
    (net (code "6") (name "AVDD") (class "Default")
      (node (ref "AVDD") (pin "TP") (pinfunction "P$1_TP") (pintype "bidirectional"))
      (node (ref "C23") (pin "1") (pinfunction "1_1") (pintype "passive"))
      (node (ref "C35") (pin "1") (pinfunction "1_1") (pintype "passive"))
      (node (ref "IC2") (pin "43") (pinfunction "ADC_AVDD_43") (pintype "bidirectional"))
      (node (ref "IC3") (pin "1") (pinfunction "OUT_1") (pintype "output"))
      (node (ref "IC3") (pin "4") (pinfunction "-IN_4") (pintype "input"))
    )
    (net (code "7") (name "CC1") (class "Default")
      (node (ref "R24") (pin "1") (pinfunction "1_1") (pintype "passive"))
      (node (ref "USBC") (pin "A5") (pinfunction "CC1_A5") (pintype "passive"))
    )
    (net (code "8") (name "CC2") (class "Default")
      (node (ref "R23") (pin "1") (pinfunction "1_1") (pintype "passive"))
      (node (ref "USBC") (pin "B5") (pinfunction "CC2_B5") (pintype "passive"))
    )
    (net (code "9") (name "DIO_RESET") (class "Default")
      (node (ref "IC2") (pin "9") (pinfunction "GPIO7_9") (pintype "bidirectional"))
      (node (ref "IC8") (pin "13") (pinfunction "~{RESET}_13") (pintype "input"))
    )
    (net (code "10") (name "DP_N") (class "Default")
      (node (ref "ESD1") (pin "3") (pinfunction "C2_3") (pintype "bidirectional"))
      (node (ref "R21") (pin "1") (pinfunction "1_1") (pintype "passive"))
      (node (ref "USBC") (pin "A7") (pinfunction "D-1_A7") (pintype "passive"))
      (node (ref "USBC") (pin "B7") (pinfunction "D-2_B7") (pintype "passive"))
    )
    (net (code "11") (name "DP_P") (class "Default")
      (node (ref "ESD1") (pin "2") (pinfunction "C1_2") (pintype "bidirectional"))
      (node (ref "R22") (pin "1") (pinfunction "1_1") (pintype "passive"))
      (node (ref "USBC") (pin "A6") (pinfunction "D+1_A6") (pintype "passive"))
      (node (ref "USBC") (pin "B6") (pinfunction "D+2_B6") (pintype "passive"))
    )
    (net (code "12") (name "DSP_RES") (class "Default")
      (node (ref "IC2") (pin "34") (pinfunction "GPIO22_34") (pintype "bidirectional"))
      (node (ref "J3") (pin "9") (pinfunction "9_9") (pintype "bidirectional"))
    )
    (net (code "13") (name "EXP_RST") (class "Default")
      (node (ref "IC2") (pin "35") (pinfunction "GPIO23_35") (pintype "bidirectional"))
      (node (ref "J3") (pin "11") (pinfunction "11_11") (pintype "bidirectional"))
    )
    (net (code "14") (name "GND") (class "Default")
      (node (ref "C1") (pin "2") (pinfunction "2_2") (pintype "passive"))
      (node (ref "C10") (pin "2") (pinfunction "2_2") (pintype "passive"))
      (node (ref "C11") (pin "2") (pinfunction "2_2") (pintype "passive"))
      (node (ref "C12") (pin "2") (pinfunction "2_2") (pintype "passive"))
      (node (ref "C13") (pin "2") (pinfunction "2_2") (pintype "passive"))
      (node (ref "C14") (pin "2") (pinfunction "2_2") (pintype "passive"))
      (node (ref "C15") (pin "2") (pinfunction "2_2") (pintype "passive"))
      (node (ref "C16") (pin "2") (pinfunction "2_2") (pintype "passive"))
      (node (ref "C17") (pin "2") (pinfunction "2_2") (pintype "passive"))
      (node (ref "C18") (pin "2") (pinfunction "2_2") (pintype "passive"))
      (node (ref "C19") (pin "2") (pinfunction "2_2") (pintype "passive"))
      (node (ref "C2") (pin "2") (pinfunction "2_2") (pintype "passive"))
      (node (ref "C20") (pin "2") (pinfunction "2_2") (pintype "passive"))
      (node (ref "C21") (pin "2") (pinfunction "2_2") (pintype "passive"))
      (node (ref "C22") (pin "2") (pinfunction "2_2") (pintype "passive"))
      (node (ref "C23") (pin "2") (pinfunction "2_2") (pintype "passive"))
      (node (ref "C24") (pin "2") (pinfunction "2_2") (pintype "passive"))
      (node (ref "C25") (pin "2") (pinfunction "2_2") (pintype "passive"))
      (node (ref "C26") (pin "2") (pinfunction "2_2") (pintype "passive"))
      (node (ref "C27") (pin "2") (pinfunction "2_2") (pintype "passive"))
      (node (ref "C28") (pin "2") (pinfunction "2_2") (pintype "passive"))
      (node (ref "C29") (pin "2") (pinfunction "2_2") (pintype "passive"))
      (node (ref "C30") (pin "2") (pinfunction "2_2") (pintype "passive"))
      (node (ref "C31") (pin "2") (pinfunction "2_2") (pintype "passive"))
      (node (ref "C32") (pin "2") (pinfunction "2_2") (pintype "passive"))
      (node (ref "C33") (pin "2") (pinfunction "2_2") (pintype "passive"))
      (node (ref "C34") (pin "2") (pinfunction "2_2") (pintype "passive"))
      (node (ref "C35") (pin "2") (pinfunction "2_2") (pintype "passive"))
      (node (ref "C36") (pin "2") (pinfunction "2_2") (pintype "passive"))
      (node (ref "C37") (pin "2") (pinfunction "2_2") (pintype "passive"))
      (node (ref "C38") (pin "2") (pinfunction "2_2") (pintype "passive"))
      (node (ref "C39") (pin "2") (pinfunction "2_2") (pintype "passive"))
      (node (ref "C40") (pin "2") (pinfunction "2_2") (pintype "passive"))
      (node (ref "C44") (pin "2") (pinfunction "2_2") (pintype "passive"))
      (node (ref "C45") (pin "2") (pinfunction "2_2") (pintype "passive"))
      (node (ref "C46") (pin "2") (pinfunction "2_2") (pintype "passive"))
      (node (ref "C47") (pin "2") (pinfunction "2_2") (pintype "passive"))
      (node (ref "C48") (pin "2") (pinfunction "2_2") (pintype "passive"))
      (node (ref "C49") (pin "2") (pinfunction "2_2") (pintype "passive"))
      (node (ref "C5") (pin "1") (pinfunction "1_1") (pintype "passive"))
      (node (ref "C53") (pin "2") (pinfunction "2_2") (pintype "passive"))
      (node (ref "C54") (pin "2") (pinfunction "2_2") (pintype "passive"))
      (node (ref "C55") (pin "2") (pinfunction "2_2") (pintype "passive"))
      (node (ref "C56") (pin "2") (pinfunction "2_2") (pintype "passive"))
      (node (ref "C57") (pin "2") (pinfunction "2_2") (pintype "passive"))
      (node (ref "C6") (pin "2") (pinfunction "2_2") (pintype "passive"))
      (node (ref "C7") (pin "2") (pinfunction "2_2") (pintype "passive"))
      (node (ref "C8") (pin "2") (pinfunction "2_2") (pintype "passive"))
      (node (ref "C9") (pin "2") (pinfunction "2_2") (pintype "passive"))
      (node (ref "DBG1") (pin "2") (pinfunction "P$2_2") (pintype "bidirectional"))
      (node (ref "DBG1") (pin "4") (pinfunction "P$4_4") (pintype "bidirectional"))
      (node (ref "DBG2") (pin "2") (pinfunction "P$2_2") (pintype "bidirectional"))
      (node (ref "DBG2") (pin "4") (pinfunction "P$4_4") (pintype "bidirectional"))
      (node (ref "ESD1") (pin "1") (pinfunction "A_1") (pintype "bidirectional"))
      (node (ref "ETH1") (pin "8") (pinfunction "SHIELD-P8_8") (pintype "passive"))
      (node (ref "GND") (pin "TP") (pinfunction "P$1_TP") (pintype "bidirectional"))
      (node (ref "GND-3") (pin "TP") (pinfunction "P$1_TP") (pintype "bidirectional"))
      (node (ref "GND-5") (pin "TP") (pinfunction "P$1_TP") (pintype "bidirectional"))
      (node (ref "IC1") (pin "14") (pinfunction "AGND_14") (pintype "power_in"))
      (node (ref "IC1") (pin "16") (pinfunction "AGND_16") (pintype "power_in"))
      (node (ref "IC1") (pin "19") (pinfunction "AGND_19") (pintype "power_in"))
      (node (ref "IC1") (pin "29") (pinfunction "GND_29") (pintype "passive"))
      (node (ref "IC1") (pin "3") (pinfunction "AGND_3") (pintype "power_in"))
      (node (ref "IC1") (pin "48") (pinfunction "AGND_48") (pintype "power_in"))
      (node (ref "IC1") (pin "9") (pinfunction "AGND_9") (pintype "power_in"))
      (node (ref "IC2") (pin "19") (pinfunction "TESTEN_19") (pintype "bidirectional"))
      (node (ref "IC2") (pin "57") (pinfunction "GND_57") (pintype "bidirectional"))
      (node (ref "IC3") (pin "5") (pinfunction "V-_5") (pintype "power_in"))
      (node (ref "IC4") (pin "4") (pinfunction "GND_4") (pintype "power_in"))
      (node (ref "IC5") (pin "4") (pinfunction "GND_4") (pintype "bidirectional"))
      (node (ref "IC6") (pin "2") (pinfunction "A1_2") (pintype "bidirectional"))
      (node (ref "IC6") (pin "3") (pinfunction "A2_3") (pintype "bidirectional"))
      (node (ref "IC6") (pin "4") (pinfunction "GND_4") (pintype "power_in"))
      (node (ref "IC6") (pin "7") (pinfunction "WP_7") (pintype "bidirectional"))
      (node (ref "IC6") (pin "9") (pinfunction "GND_9") (pintype "power_in"))
      (node (ref "IC7") (pin "4") (pinfunction "GND_4") (pintype "bidirectional"))
      (node (ref "IC8") (pin "23") (pinfunction "VSS_23") (pintype "power_in"))
      (node (ref "IC8") (pin "25") (pinfunction "VSS_25") (pintype "power_in"))
      (node (ref "J1") (pin "13") (pinfunction "13_13") (pintype "bidirectional"))
      (node (ref "J2") (pin "1") (pinfunction "1_1") (pintype "bidirectional"))
      (node (ref "J2") (pin "13") (pinfunction "13_13") (pintype "bidirectional"))
      (node (ref "J2") (pin "14") (pinfunction "14_14") (pintype "bidirectional"))
      (node (ref "J2") (pin "2") (pinfunction "2_2") (pintype "bidirectional"))
      (node (ref "J3") (pin "1") (pinfunction "1_1") (pintype "bidirectional"))
      (node (ref "J3") (pin "13") (pinfunction "13_13") (pintype "bidirectional"))
      (node (ref "J3") (pin "14") (pinfunction "14_14") (pintype "bidirectional"))
      (node (ref "J3") (pin "2") (pinfunction "2_2") (pintype "bidirectional"))
      (node (ref "R11") (pin "1") (pinfunction "1_1") (pintype "passive"))
      (node (ref "R20") (pin "2") (pinfunction "2_2") (pintype "passive"))
      (node (ref "R23") (pin "2") (pinfunction "2_2") (pintype "passive"))
      (node (ref "R24") (pin "2") (pinfunction "2_2") (pintype "passive"))
      (node (ref "R26") (pin "2") (pinfunction "2_2") (pintype "passive"))
      (node (ref "R28") (pin "1") (pinfunction "1_1") (pintype "passive"))
      (node (ref "R32") (pin "2") (pinfunction "2_2") (pintype "passive"))
      (node (ref "R33") (pin "2") (pinfunction "2_2") (pintype "passive"))
      (node (ref "R37") (pin "2") (pinfunction "2_2") (pintype "passive"))
      (node (ref "R39") (pin "2") (pinfunction "2_2") (pintype "passive"))
      (node (ref "R44") (pin "2") (pinfunction "2_2") (pintype "passive"))
      (node (ref "R49") (pin "1") (pinfunction "1_1") (pintype "passive"))
      (node (ref "REF1") (pin "2") (pinfunction "A_2") (pintype "passive"))
      (node (ref "REF1") (pin "3") (pinfunction "A_3") (pintype "passive"))
      (node (ref "RESET") (pin "2") (pinfunction "S_2") (pintype "passive"))
      (node (ref "USBC") (pin "A1") (pinfunction "GND_A1") (pintype "passive"))
      (node (ref "USBC") (pin "A12") (pinfunction "GND1_A12") (pintype "passive"))
      (node (ref "USBC") (pin "B1") (pinfunction "GND3_B1") (pintype "passive"))
      (node (ref "USBC") (pin "B12") (pinfunction "GND2_B12") (pintype "passive"))
      (node (ref "USB_BOOT") (pin "2") (pinfunction "S_2") (pintype "passive"))
      (node (ref "X1") (pin "2") (pinfunction "VSS_2") (pintype "power_in"))
      (node (ref "X1") (pin "4") (pinfunction "VDD_4") (pintype "power_in"))
      (node (ref "X2") (pin "2") (pinfunction "VSS_2") (pintype "power_in"))
      (node (ref "X2") (pin "4") (pinfunction "VDD_4") (pintype "power_in"))
    )
    (net (code "15") (name "I2C0_SCL") (class "Default")
      (node (ref "IC2") (pin "7") (pinfunction "GPIO5_7") (pintype "bidirectional"))
      (node (ref "J3") (pin "7") (pinfunction "7_7") (pintype "bidirectional"))
      (node (ref "R38") (pin "1") (pinfunction "1_1") (pintype "passive"))
    )
    (net (code "16") (name "I2C0_SDA") (class "Default")
      (node (ref "IC2") (pin "6") (pinfunction "GPIO4_6") (pintype "bidirectional"))
      (node (ref "J3") (pin "5") (pinfunction "5_5") (pintype "bidirectional"))
      (node (ref "R38") (pin "2") (pinfunction "2_2") (pintype "passive"))
    )
    (net (code "17") (name "I2C1_SCL") (class "Default")
      (node (ref "IC2") (pin "5") (pinfunction "GPIO3_5") (pintype "bidirectional"))
      (node (ref "IC6") (pin "6") (pinfunction "SCL_6") (pintype "bidirectional"))
      (node (ref "R38") (pin "3") (pinfunction "3_3") (pintype "passive"))
    )
    (net (code "18") (name "I2C1_SDA") (class "Default")
      (node (ref "IC2") (pin "4") (pinfunction "GPIO2_4") (pintype "bidirectional"))
      (node (ref "IC6") (pin "5") (pinfunction "SDA_5") (pintype "bidirectional"))
      (node (ref "R38") (pin "4") (pinfunction "4_4") (pintype "passive"))
    )
    (net (code "19") (name "I_MEA{slash}TX") (class "Default")
      (node (ref "IC2") (pin "40") (pinfunction "GPIO28/ADC2_40") (pintype "bidirectional"))
      (node (ref "J1") (pin "4") (pinfunction "4_4") (pintype "bidirectional"))
      (node (ref "R46") (pin "1") (pinfunction "1_1") (pintype "passive"))
    )
    (net (code "20") (name "KEY_0") (class "Default")
      (node (ref "IC2") (pin "15") (pinfunction "GPIO12_15") (pintype "bidirectional"))
      (node (ref "J3") (pin "6") (pinfunction "6_6") (pintype "bidirectional"))
    )
    (net (code "21") (name "KEY_1") (class "Default")
      (node (ref "IC2") (pin "16") (pinfunction "GPIO13_16") (pintype "bidirectional"))
      (node (ref "J3") (pin "8") (pinfunction "8_8") (pintype "bidirectional"))
    )
    (net (code "22") (name "KEY_2") (class "Default")
      (node (ref "IC2") (pin "17") (pinfunction "GPIO14_17") (pintype "bidirectional"))
      (node (ref "J3") (pin "10") (pinfunction "10_10") (pintype "bidirectional"))
    )
    (net (code "23") (name "KEY_3") (class "Default")
      (node (ref "IC2") (pin "18") (pinfunction "GPIO15_18") (pintype "bidirectional"))
      (node (ref "J3") (pin "12") (pinfunction "12_12") (pintype "bidirectional"))
    )
    (net (code "24") (name "Net-(C5-Pad2)") (class "Default")
      (node (ref "C5") (pin "2") (pinfunction "2_2") (pintype "passive"))
      (node (ref "ETH1") (pin "S1") (pinfunction "SHIELD_S1") (pintype "passive"))
      (node (ref "ETH1") (pin "S2") (pinfunction "SHIELD_S2") (pintype "passive"))
    )
    (net (code "25") (name "Net-(C42-Pad1)") (class "Default")
      (node (ref "C42") (pin "1") (pinfunction "1_1") (pintype "passive"))
      (node (ref "R41") (pin "1") (pinfunction "1_1") (pintype "passive"))
    )
    (net (code "26") (name "Net-(C51-Pad1)") (class "Default")
      (node (ref "C51") (pin "1") (pinfunction "1_1") (pintype "passive"))
      (node (ref "R34") (pin "1") (pinfunction "1_1") (pintype "passive"))
    )
    (net (code "27") (name "Net-(ETH1-GK1)") (class "Default")
      (node (ref "ETH1") (pin "10") (pinfunction "GK1_10") (pintype "passive"))
      (node (ref "R9") (pin "2") (pinfunction "2_2") (pintype "passive"))
    )
    (net (code "28") (name "Net-(ETH1-GK2)") (class "Default")
      (node (ref "ETH1") (pin "12") (pinfunction "GK2_12") (pintype "passive"))
      (node (ref "R10") (pin "2") (pinfunction "2_2") (pintype "passive"))
    )
    (net (code "29") (name "Net-(IC1-1V2O)") (class "Default")
      (node (ref "C6") (pin "1") (pinfunction "1_1") (pintype "passive"))
      (node (ref "IC1") (pin "22") (pinfunction "1V2O_22") (pintype "output"))
    )
    (net (code "30") (name "Net-(IC1-EXRES1)") (class "Default")
      (node (ref "IC1") (pin "10") (pinfunction "EXRES1_10") (pintype "bidirectional"))
      (node (ref "R11") (pin "2") (pinfunction "2_2") (pintype "passive"))
    )
    (net (code "31") (name "Net-(IC1-TOCAP)") (class "Default")
      (node (ref "C7") (pin "1") (pinfunction "1_1") (pintype "passive"))
      (node (ref "IC1") (pin "20") (pinfunction "TOCAP_20") (pintype "output"))
    )
    (net (code "32") (name "Net-(IC1-XI)") (class "Default")
      (node (ref "IC1") (pin "30") (pinfunction "XI_30") (pintype "input"))
      (node (ref "R13") (pin "2") (pinfunction "2_2") (pintype "passive"))
    )
    (net (code "33") (name "Net-(IC1-XO)") (class "Default")
      (node (ref "IC1") (pin "31") (pinfunction "XO_31") (pintype "output"))
      (node (ref "R12") (pin "2") (pinfunction "2_2") (pintype "passive"))
    )
    (net (code "34") (name "Net-(IC2-RUN)") (class "Default")
      (node (ref "IC2") (pin "26") (pinfunction "RUN_26") (pintype "bidirectional"))
      (node (ref "R50") (pin "2") (pinfunction "2_2") (pintype "passive"))
      (node (ref "RESET") (pin "1") (pinfunction "P_1") (pintype "passive"))
    )
    (net (code "35") (name "Net-(IC2-USB_DM)") (class "Default")
      (node (ref "IC2") (pin "46") (pinfunction "USB_DM_46") (pintype "bidirectional"))
      (node (ref "R21") (pin "2") (pinfunction "2_2") (pintype "passive"))
    )
    (net (code "36") (name "Net-(IC2-USB_DP)") (class "Default")
      (node (ref "IC2") (pin "47") (pinfunction "USB_DP_47") (pintype "bidirectional"))
      (node (ref "R22") (pin "2") (pinfunction "2_2") (pintype "passive"))
    )
    (net (code "37") (name "Net-(IC3-+IN)") (class "Default")
      (node (ref "C21") (pin "1") (pinfunction "1_1") (pintype "passive"))
      (node (ref "C22") (pin "1") (pinfunction "1_1") (pintype "passive"))
      (node (ref "IC3") (pin "3") (pinfunction "+IN_3") (pintype "input"))
      (node (ref "R17") (pin "1") (pinfunction "1_1") (pintype "passive"))
      (node (ref "REF1") (pin "1") (pinfunction "C_1") (pintype "passive"))
      (node (ref "VREF") (pin "TP") (pinfunction "P$1_TP") (pintype "bidirectional"))
    )
    (net (code "38") (name "Net-(IC5-AAM)") (class "Default")
      (node (ref "IC5") (pin "1") (pinfunction "AAM_1") (pintype "bidirectional"))
      (node (ref "R32") (pin "1") (pinfunction "1_1") (pintype "passive"))
      (node (ref "R45") (pin "2") (pinfunction "2_2") (pintype "passive"))
    )
    (net (code "39") (name "Net-(IC5-BST)") (class "Default")
      (node (ref "IC5") (pin "5") (pinfunction "BST_5") (pintype "bidirectional"))
      (node (ref "R41") (pin "2") (pinfunction "2_2") (pintype "passive"))
    )
    (net (code "40") (name "Net-(IC5-EN)") (class "Default")
      (node (ref "IC5") (pin "6") (pinfunction "EN_6") (pintype "bidirectional"))
      (node (ref "R30") (pin "2") (pinfunction "2_2") (pintype "passive"))
    )
    (net (code "41") (name "Net-(IC5-FB)") (class "Default")
      (node (ref "IC5") (pin "8") (pinfunction "FB_8") (pintype "bidirectional"))
      (node (ref "R42") (pin "1") (pinfunction "1_1") (pintype "passive"))
    )
    (net (code "42") (name "Net-(IC5-SW)") (class "Default")
      (node (ref "C42") (pin "2") (pinfunction "2_2") (pintype "passive"))
      (node (ref "IC5") (pin "3") (pinfunction "SW_3") (pintype "bidirectional"))
      (node (ref "L3") (pin "1") (pinfunction "1_1") (pintype "passive"))
      (node (ref "SW3") (pin "TP") (pinfunction "P$1_TP") (pintype "bidirectional"))
    )
    (net (code "43") (name "Net-(IC5-VCC)") (class "Default")
      (node (ref "C40") (pin "1") (pinfunction "1_1") (pintype "passive"))
      (node (ref "IC5") (pin "7") (pinfunction "VCC_7") (pintype "bidirectional"))
      (node (ref "R45") (pin "1") (pinfunction "1_1") (pintype "passive"))
    )
    (net (code "44") (name "Net-(IC6-A0)") (class "Default")
      (node (ref "IC6") (pin "1") (pinfunction "A0_1") (pintype "bidirectional"))
      (node (ref "R27") (pin "1") (pinfunction "1_1") (pintype "passive"))
      (node (ref "R28") (pin "2") (pinfunction "2_2") (pintype "passive"))
    )
    (net (code "45") (name "Net-(IC7-AAM)") (class "Default")
      (node (ref "IC7") (pin "1") (pinfunction "AAM_1") (pintype "bidirectional"))
      (node (ref "R29") (pin "2") (pinfunction "2_2") (pintype "passive"))
      (node (ref "R33") (pin "1") (pinfunction "1_1") (pintype "passive"))
    )
    (net (code "46") (name "Net-(IC7-BST)") (class "Default")
      (node (ref "IC7") (pin "5") (pinfunction "BST_5") (pintype "bidirectional"))
      (node (ref "R34") (pin "2") (pinfunction "2_2") (pintype "passive"))
    )
    (net (code "47") (name "Net-(IC7-EN)") (class "Default")
      (node (ref "IC7") (pin "6") (pinfunction "EN_6") (pintype "bidirectional"))
      (node (ref "R31") (pin "2") (pinfunction "2_2") (pintype "passive"))
    )
    (net (code "48") (name "Net-(IC7-FB)") (class "Default")
      (node (ref "IC7") (pin "8") (pinfunction "FB_8") (pintype "bidirectional"))
      (node (ref "R35") (pin "1") (pinfunction "1_1") (pintype "passive"))
    )
    (net (code "49") (name "Net-(IC7-SW)") (class "Default")
      (node (ref "C51") (pin "2") (pinfunction "2_2") (pintype "passive"))
      (node (ref "IC7") (pin "3") (pinfunction "SW_3") (pintype "bidirectional"))
      (node (ref "L2") (pin "1") (pinfunction "1_1") (pintype "passive"))
      (node (ref "SW5") (pin "TP") (pinfunction "P$1_TP") (pintype "bidirectional"))
    )
    (net (code "50") (name "Net-(IC7-VCC)") (class "Default")
      (node (ref "C49") (pin "1") (pinfunction "1_1") (pintype "passive"))
      (node (ref "IC7") (pin "7") (pinfunction "VCC_7") (pintype "bidirectional"))
      (node (ref "R29") (pin "1") (pinfunction "1_1") (pintype "passive"))
    )
    (net (code "51") (name "Net-(VFB3-P$1)") (class "Default")
      (node (ref "C43") (pin "2") (pinfunction "2_2") (pintype "passive"))
      (node (ref "R42") (pin "2") (pinfunction "2_2") (pintype "passive"))
      (node (ref "R43") (pin "2") (pinfunction "2_2") (pintype "passive"))
      (node (ref "R44") (pin "1") (pinfunction "1_1") (pintype "passive"))
      (node (ref "VFB3") (pin "TP") (pinfunction "P$1_TP") (pintype "bidirectional"))
    )
    (net (code "52") (name "Net-(VFB5-P$1)") (class "Default")
      (node (ref "C52") (pin "2") (pinfunction "2_2") (pintype "passive"))
      (node (ref "R35") (pin "2") (pinfunction "2_2") (pintype "passive"))
      (node (ref "R36") (pin "2") (pinfunction "2_2") (pintype "passive"))
      (node (ref "R37") (pin "1") (pinfunction "1_1") (pintype "passive"))
      (node (ref "VFB5") (pin "TP") (pinfunction "P$1_TP") (pintype "bidirectional"))
    )
    (net (code "53") (name "Net-(X1-CON)") (class "Default")
      (node (ref "C8") (pin "1") (pinfunction "1_1") (pintype "passive"))
      (node (ref "R12") (pin "1") (pinfunction "1_1") (pintype "passive"))
      (node (ref "X1") (pin "1") (pinfunction "CON_1") (pintype "input"))
    )
    (net (code "54") (name "Net-(X1-OUT)") (class "Default")
      (node (ref "C9") (pin "1") (pinfunction "1_1") (pintype "passive"))
      (node (ref "R13") (pin "1") (pinfunction "1_1") (pintype "passive"))
      (node (ref "X1") (pin "3") (pinfunction "OUT_3") (pintype "output"))
    )
    (net (code "55") (name "Net-(X2-OUT)") (class "Default")
      (node (ref "C20") (pin "1") (pinfunction "1_1") (pintype "passive"))
      (node (ref "R15") (pin "2") (pinfunction "2_2") (pintype "passive"))
      (node (ref "R16") (pin "1") (pinfunction "1_1") (pintype "passive"))
      (node (ref "X2") (pin "3") (pinfunction "OUT_3") (pintype "output"))
    )
    (net (code "56") (name "PWR_DETECT") (class "Default")
      (node (ref "12VFB") (pin "TP") (pinfunction "P$1_TP") (pintype "bidirectional"))
      (node (ref "IC2") (pin "41") (pinfunction "GPIO29/ADC3_41") (pintype "bidirectional"))
      (node (ref "R48") (pin "1") (pinfunction "1_1") (pintype "passive"))
      (node (ref "R49") (pin "2") (pinfunction "2_2") (pintype "passive"))
    )
    (net (code "57") (name "QSPI_SCLK") (class "Default")
      (node (ref "IC2") (pin "52") (pinfunction "QSPI_SCLK_52") (pintype "bidirectional"))
      (node (ref "IC4") (pin "6") (pinfunction "CLK_6") (pintype "bidirectional"))
    )
    (net (code "58") (name "QSPI_SD0") (class "Default")
      (node (ref "IC2") (pin "53") (pinfunction "QSPI_SD0_53") (pintype "bidirectional"))
      (node (ref "IC4") (pin "5") (pinfunction "DI/IO0_5") (pintype "bidirectional"))
    )
    (net (code "59") (name "QSPI_SD1") (class "Default")
      (node (ref "IC2") (pin "55") (pinfunction "QSPI_SD1_55") (pintype "bidirectional"))
      (node (ref "IC4") (pin "2") (pinfunction "DO/IO1_2") (pintype "bidirectional"))
    )
    (net (code "60") (name "QSPI_SD2") (class "Default")
      (node (ref "IC2") (pin "54") (pinfunction "QSPI_SD2_54") (pintype "bidirectional"))
      (node (ref "IC4") (pin "3") (pinfunction "~{WP}/IO2_3") (pintype "bidirectional"))
    )
    (net (code "61") (name "QSPI_SD3") (class "Default")
      (node (ref "IC2") (pin "51") (pinfunction "QSPI_SD3_51") (pintype "bidirectional"))
      (node (ref "IC4") (pin "7") (pinfunction "~{HOLD}/IO3_7") (pintype "bidirectional"))
    )
    (net (code "62") (name "RCT") (class "Default")
      (node (ref "C1") (pin "1") (pinfunction "1_1") (pintype "passive"))
      (node (ref "ETH1") (pin "5") (pinfunction "RCT_5") (pintype "passive"))
      (node (ref "R5") (pin "1") (pinfunction "1_1") (pintype "passive"))
      (node (ref "R6") (pin "1") (pinfunction "1_1") (pintype "passive"))
    )
    (net (code "63") (name "RDC_RD_N") (class "Default")
      (node (ref "C3") (pin "1") (pinfunction "1_1") (pintype "passive"))
      (node (ref "R4") (pin "2") (pinfunction "2_2") (pintype "passive"))
      (node (ref "R5") (pin "2") (pinfunction "2_2") (pintype "passive"))
    )
    (net (code "64") (name "RDC_RD_P") (class "Default")
      (node (ref "C4") (pin "1") (pinfunction "1_1") (pintype "passive"))
      (node (ref "R3") (pin "2") (pinfunction "2_2") (pintype "passive"))
      (node (ref "R6") (pin "2") (pinfunction "2_2") (pintype "passive"))
    )
    (net (code "65") (name "RD_N") (class "Default")
      (node (ref "C3") (pin "2") (pinfunction "2_2") (pintype "passive"))
      (node (ref "ETH1") (pin "6") (pinfunction "RD-_6") (pintype "passive"))
    )
    (net (code "66") (name "RD_P") (class "Default")
      (node (ref "C4") (pin "2") (pinfunction "2_2") (pintype "passive"))
      (node (ref "ETH1") (pin "4") (pinfunction "RD+_4") (pintype "passive"))
    )
    (net (code "67") (name "REL_0") (class "Default")
      (node (ref "IC8") (pin "15") (pinfunction "GPA0_15") (pintype "bidirectional"))
      (node (ref "J1") (pin "12") (pinfunction "12_12") (pintype "bidirectional"))
    )
    (net (code "68") (name "REL_1") (class "Default")
      (node (ref "IC8") (pin "16") (pinfunction "GPA1_16") (pintype "bidirectional"))
      (node (ref "J1") (pin "11") (pinfunction "11_11") (pintype "bidirectional"))
    )
    (net (code "69") (name "REL_2") (class "Default")
      (node (ref "IC8") (pin "17") (pinfunction "GPA2_17") (pintype "bidirectional"))
      (node (ref "J1") (pin "10") (pinfunction "10_10") (pintype "bidirectional"))
    )
    (net (code "70") (name "REL_3") (class "Default")
      (node (ref "IC8") (pin "18") (pinfunction "GPA3_18") (pintype "bidirectional"))
      (node (ref "J1") (pin "9") (pinfunction "9_9") (pintype "bidirectional"))
    )
    (net (code "71") (name "REL_4") (class "Default")
      (node (ref "IC8") (pin "19") (pinfunction "GPA4_19") (pintype "bidirectional"))
      (node (ref "J1") (pin "8") (pinfunction "8_8") (pintype "bidirectional"))
    )
    (net (code "72") (name "REL_5") (class "Default")
      (node (ref "IC8") (pin "20") (pinfunction "GPA5_20") (pintype "bidirectional"))
      (node (ref "J1") (pin "7") (pinfunction "7_7") (pintype "bidirectional"))
    )
    (net (code "73") (name "REL_6") (class "Default")
      (node (ref "IC8") (pin "21") (pinfunction "GPA6_21") (pintype "bidirectional"))
      (node (ref "J1") (pin "6") (pinfunction "6_6") (pintype "bidirectional"))
    )
    (net (code "74") (name "REL_7") (class "Default")
      (node (ref "IC8") (pin "22") (pinfunction "GPA7_22") (pintype "bidirectional"))
      (node (ref "J1") (pin "5") (pinfunction "5_5") (pintype "bidirectional"))
    )
    (net (code "75") (name "RP_XI") (class "Default")
      (node (ref "C19") (pin "1") (pinfunction "1_1") (pintype "passive"))
      (node (ref "IC2") (pin "20") (pinfunction "XIN_20") (pintype "bidirectional"))
      (node (ref "R15") (pin "1") (pinfunction "1_1") (pintype "passive"))
      (node (ref "X2") (pin "1") (pinfunction "CON_1") (pintype "input"))
    )
    (net (code "76") (name "RP_XO") (class "Default")
      (node (ref "IC2") (pin "21") (pinfunction "XOUT_21") (pintype "bidirectional"))
      (node (ref "R16") (pin "2") (pinfunction "2_2") (pintype "passive"))
    )
    (net (code "77") (name "RX_RD_N") (class "Default")
      (node (ref "IC1") (pin "5") (pinfunction "RXN_5") (pintype "input"))
      (node (ref "R4") (pin "1") (pinfunction "1_1") (pintype "passive"))
    )
    (net (code "78") (name "RX_RD_P") (class "Default")
      (node (ref "IC1") (pin "6") (pinfunction "RXP_6") (pintype "input"))
      (node (ref "R3") (pin "1") (pinfunction "1_1") (pintype "passive"))
    )
    (net (code "79") (name "SPI0_MISO") (class "Default")
      (node (ref "IC1") (pin "34") (pinfunction "MISO_34") (pintype "output"))
      (node (ref "IC2") (pin "27") (pinfunction "GPIO16_27") (pintype "bidirectional"))
    )
    (net (code "80") (name "SPI0_MOSI") (class "Default")
      (node (ref "IC1") (pin "35") (pinfunction "MOSI_35") (pintype "input"))
      (node (ref "IC2") (pin "30") (pinfunction "GPIO19_30") (pintype "bidirectional"))
    )
    (net (code "81") (name "SPI0_SCK") (class "Default")
      (node (ref "IC1") (pin "33") (pinfunction "SCLK_33") (pintype "input"))
      (node (ref "IC2") (pin "29") (pinfunction "GPIO18_29") (pintype "bidirectional"))
    )
    (net (code "82") (name "SPI1_MISO") (class "Default")
      (node (ref "IC2") (pin "11") (pinfunction "GPIO8_11") (pintype "bidirectional"))
      (node (ref "IC8") (pin "12") (pinfunction "SO_12") (pintype "output"))
      (node (ref "J2") (pin "7") (pinfunction "7_7") (pintype "bidirectional"))
    )
    (net (code "83") (name "SPI1_MOSI") (class "Default")
      (node (ref "IC2") (pin "14") (pinfunction "GPIO11_14") (pintype "bidirectional"))
      (node (ref "IC8") (pin "11") (pinfunction "SI_11") (pintype "input"))
      (node (ref "J2") (pin "5") (pinfunction "5_5") (pintype "bidirectional"))
    )
    (net (code "84") (name "SPI1_SCK") (class "Default")
      (node (ref "IC2") (pin "13") (pinfunction "GPIO10_13") (pintype "bidirectional"))
      (node (ref "IC8") (pin "10") (pinfunction "SCK_10") (pintype "input"))
      (node (ref "J2") (pin "9") (pinfunction "9_9") (pintype "bidirectional"))
    )
    (net (code "85") (name "SWCLK") (class "Default")
      (node (ref "DBG2") (pin "1") (pinfunction "P$1_1") (pintype "bidirectional"))
      (node (ref "IC2") (pin "24") (pinfunction "SWCLK_24") (pintype "bidirectional"))
    )
    (net (code "86") (name "SWDIO") (class "Default")
      (node (ref "DBG2") (pin "3") (pinfunction "P$3_3") (pintype "bidirectional"))
      (node (ref "IC2") (pin "25") (pinfunction "SWDIO_25") (pintype "bidirectional"))
    )
    (net (code "87") (name "TCT") (class "Default")
      (node (ref "C2") (pin "1") (pinfunction "1_1") (pintype "passive"))
      (node (ref "ETH1") (pin "2") (pinfunction "TCT_2") (pintype "passive"))
      (node (ref "R40") (pin "1") (pinfunction "1_1") (pintype "passive"))
    )
    (net (code "88") (name "TD_N") (class "Default")
      (node (ref "ETH1") (pin "3") (pinfunction "TD-_3") (pintype "passive"))
      (node (ref "R1") (pin "2") (pinfunction "2_2") (pintype "passive"))
      (node (ref "R8") (pin "1") (pinfunction "1_1") (pintype "passive"))
    )
    (net (code "89") (name "TD_P") (class "Default")
      (node (ref "ETH1") (pin "1") (pinfunction "TD+_1") (pintype "passive"))
      (node (ref "R2") (pin "2") (pinfunction "2_2") (pintype "passive"))
      (node (ref "R7") (pin "1") (pinfunction "1_1") (pintype "passive"))
    )
    (net (code "90") (name "TX_TD_N") (class "Default")
      (node (ref "IC1") (pin "1") (pinfunction "TXN_1") (pintype "output"))
      (node (ref "R1") (pin "1") (pinfunction "1_1") (pintype "passive"))
    )
    (net (code "91") (name "TX_TD_P") (class "Default")
      (node (ref "IC1") (pin "2") (pinfunction "TXP_2") (pintype "output"))
      (node (ref "R2") (pin "1") (pinfunction "1_1") (pintype "passive"))
    )
    (net (code "92") (name "UART0_RX") (class "Default")
      (node (ref "DBG1") (pin "1") (pinfunction "P$1_1") (pintype "bidirectional"))
      (node (ref "IC2") (pin "2") (pinfunction "GPIO0_2") (pintype "bidirectional"))
      (node (ref "R47") (pin "2") (pinfunction "2_2") (pintype "passive"))
    )
    (net (code "93") (name "UART0_TX") (class "Default")
      (node (ref "DBG1") (pin "3") (pinfunction "P$3_3") (pintype "bidirectional"))
      (node (ref "IC2") (pin "3") (pinfunction "GPIO1_3") (pintype "bidirectional"))
      (node (ref "R46") (pin "2") (pinfunction "2_2") (pintype "passive"))
    )
    (net (code "94") (name "USB_BOOT") (class "Default")
      (node (ref "R19") (pin "1") (pinfunction "1_1") (pintype "passive"))
      (node (ref "USB_BOOT") (pin "1") (pinfunction "P_1") (pintype "passive"))
    )
    (net (code "95") (name "USB_SHIELD") (class "Default")
      (node (ref "C54") (pin "1") (pinfunction "1_1") (pintype "passive"))
      (node (ref "R39") (pin "1") (pinfunction "1_1") (pintype "passive"))
      (node (ref "USBC") (pin "S1") (pinfunction "SHIELD_S1") (pintype "passive"))
      (node (ref "USBC") (pin "S2") (pinfunction "SHIELD_S2") (pintype "passive"))
      (node (ref "USBC") (pin "S3") (pinfunction "SHIELD_S3") (pintype "passive"))
      (node (ref "USBC") (pin "S4") (pinfunction "SHIELD_S4") (pintype "passive"))
    )
    (net (code "96") (name "VBUS") (class "Default")
      (node (ref "C26") (pin "1") (pinfunction "1_1") (pintype "passive"))
      (node (ref "C27") (pin "1") (pinfunction "1_1") (pintype "passive"))
      (node (ref "ESD1") (pin "4") (pinfunction "C3_4") (pintype "bidirectional"))
      (node (ref "R20") (pin "1") (pinfunction "1_1") (pintype "passive"))
      (node (ref "R25") (pin "1") (pinfunction "1_1") (pintype "passive"))
      (node (ref "USBC") (pin "A4") (pinfunction "VBUS_A4") (pintype "passive"))
      (node (ref "USBC") (pin "A9") (pinfunction "VBUS1_A9") (pintype "passive"))
      (node (ref "USBC") (pin "B4") (pinfunction "VBUS3_B4") (pintype "passive"))
      (node (ref "USBC") (pin "B9") (pinfunction "VBUS2_B9") (pintype "passive"))
      (node (ref "VBUS") (pin "TP") (pinfunction "P$1_TP") (pintype "bidirectional"))
    )
    (net (code "97") (name "V_MEA{slash}RX") (class "Default")
      (node (ref "IC2") (pin "39") (pinfunction "GPIO27/ADC1_39") (pintype "bidirectional"))
      (node (ref "J1") (pin "3") (pinfunction "3_3") (pintype "bidirectional"))
      (node (ref "R47") (pin "1") (pinfunction "1_1") (pintype "passive"))
    )
    (net (code "98") (name "V_USB") (class "Default")
      (node (ref "IC2") (pin "38") (pinfunction "GPIO26/ADC0_38") (pintype "bidirectional"))
      (node (ref "R25") (pin "2") (pinfunction "2_2") (pintype "passive"))
      (node (ref "R26") (pin "1") (pinfunction "1_1") (pintype "passive"))
    )
    (net (code "99") (name "unconnected-(IC1-DNC-Pad7)") (class "Default")
      (node (ref "IC1") (pin "7") (pinfunction "DNC_7") (pintype "bidirectional"))
    )
    (net (code "100") (name "unconnected-(IC1-DUPLED-Pad26)") (class "Default")
      (node (ref "IC1") (pin "26") (pinfunction "DUPLED_26") (pintype "output"))
    )
    (net (code "101") (name "unconnected-(IC1-RSVD1-Pad23)") (class "Default")
      (node (ref "IC1") (pin "23") (pinfunction "RSVD1_23") (pintype "input"))
    )
    (net (code "102") (name "unconnected-(IC1-RSVD2-Pad38)") (class "Default")
      (node (ref "IC1") (pin "38") (pinfunction "RSVD2_38") (pintype "input"))
    )
    (net (code "103") (name "unconnected-(IC1-RSVD3-Pad39)") (class "Default")
      (node (ref "IC1") (pin "39") (pinfunction "RSVD3_39") (pintype "input"))
    )
    (net (code "104") (name "unconnected-(IC1-RSVD4-Pad40)") (class "Default")
      (node (ref "IC1") (pin "40") (pinfunction "RSVD4_40") (pintype "input"))
    )
    (net (code "105") (name "unconnected-(IC1-RSVD5-Pad41)") (class "Default")
      (node (ref "IC1") (pin "41") (pinfunction "RSVD5_41") (pintype "input"))
    )
    (net (code "106") (name "unconnected-(IC1-RSVD6-Pad42)") (class "Default")
      (node (ref "IC1") (pin "42") (pinfunction "RSVD6_42") (pintype "input"))
    )
    (net (code "107") (name "unconnected-(IC1-SPDLED-Pad24)") (class "Default")
      (node (ref "IC1") (pin "24") (pinfunction "SPDLED_24") (pintype "output"))
    )
    (net (code "108") (name "unconnected-(IC1-VBG-Pad18)") (class "Default")
      (node (ref "IC1") (pin "18") (pinfunction "VBG_18") (pintype "output"))
    )
    (net (code "109") (name "unconnected-(IC2-GPIO24-Pad36)") (class "Default")
      (node (ref "IC2") (pin "36") (pinfunction "GPIO24_36") (pintype "bidirectional"))
    )
    (net (code "110") (name "unconnected-(IC2-GPIO25-Pad37)") (class "Default")
      (node (ref "IC2") (pin "37") (pinfunction "GPIO25_37") (pintype "bidirectional"))
    )
    (net (code "111") (name "unconnected-(IC8-GPB0-Pad24)") (class "Default")
      (node (ref "IC8") (pin "24") (pinfunction "GPB0_24") (pintype "bidirectional"))
    )
    (net (code "112") (name "unconnected-(IC8-GPB1-Pad1)") (class "Default")
      (node (ref "IC8") (pin "1") (pinfunction "GPB1_1") (pintype "bidirectional"))
    )
    (net (code "113") (name "unconnected-(IC8-GPB2-Pad2)") (class "Default")
      (node (ref "IC8") (pin "2") (pinfunction "GPB2_2") (pintype "bidirectional"))
    )
    (net (code "114") (name "unconnected-(IC8-GPB3-Pad3)") (class "Default")
      (node (ref "IC8") (pin "3") (pinfunction "GPB3_3") (pintype "bidirectional"))
    )
    (net (code "115") (name "unconnected-(IC8-GPB4-Pad4)") (class "Default")
      (node (ref "IC8") (pin "4") (pinfunction "GPB4_4") (pintype "bidirectional"))
    )
    (net (code "116") (name "unconnected-(IC8-GPB5-Pad5)") (class "Default")
      (node (ref "IC8") (pin "5") (pinfunction "GPB5_5") (pintype "bidirectional"))
    )
    (net (code "117") (name "unconnected-(IC8-GPB6-Pad6)") (class "Default")
      (node (ref "IC8") (pin "6") (pinfunction "GPB6_6") (pintype "bidirectional"))
    )
    (net (code "118") (name "unconnected-(IC8-GPB7-Pad7)") (class "Default")
      (node (ref "IC8") (pin "7") (pinfunction "GPB7_7") (pintype "bidirectional"))
    )
    (net (code "119") (name "unconnected-(IC8-INTA-Pad14)") (class "Default")
      (node (ref "IC8") (pin "14") (pinfunction "INTA_14") (pintype "output"))
    )
    (net (code "120") (name "unconnected-(J2-Pad6)") (class "Default")
      (node (ref "J2") (pin "6") (pinfunction "6_6") (pintype "bidirectional"))
    )
    (net (code "121") (name "unconnected-(J2-Pad8)") (class "Default")
      (node (ref "J2") (pin "8") (pinfunction "8_8") (pintype "bidirectional"))
    )
    (net (code "122") (name "unconnected-(J2-Pad10)") (class "Default")
      (node (ref "J2") (pin "10") (pinfunction "10_10") (pintype "bidirectional"))
    )
    (net (code "123") (name "unconnected-(J2-Pad12)") (class "Default")
      (node (ref "J2") (pin "12") (pinfunction "12_12") (pintype "bidirectional"))
    )
    (net (code "124") (name "unconnected-(USBC-SBU1-PadA8)") (class "Default")
      (node (ref "USBC") (pin "A8") (pinfunction "SBU1_A8") (pintype "passive"))
    )
    (net (code "125") (name "unconnected-(USBC-SBU2-PadB8)") (class "Default")
      (node (ref "USBC") (pin "B8") (pinfunction "SBU2_B8") (pintype "passive"))
    )
    (net (code "126") (name "~{ACT}") (class "Default")
      (node (ref "IC1") (pin "27") (pinfunction "ACTLED_27") (pintype "output"))
      (node (ref "R10") (pin "1") (pinfunction "1_1") (pintype "passive"))
    )
    (net (code "127") (name "~{INT}") (class "Default")
      (node (ref "IC1") (pin "36") (pinfunction "~{INTN}_36") (pintype "input"))
      (node (ref "IC2") (pin "32") (pinfunction "GPIO21_32") (pintype "bidirectional"))
    )
    (net (code "128") (name "~{LINK}") (class "Default")
      (node (ref "IC1") (pin "25") (pinfunction "LINKLED_25") (pintype "output"))
      (node (ref "R9") (pin "1") (pinfunction "1_1") (pintype "passive"))
    )
    (net (code "129") (name "~{QSPI_SS}") (class "Default")
      (node (ref "IC2") (pin "56") (pinfunction "QSPI_SS_N_56") (pintype "bidirectional"))
      (node (ref "IC4") (pin "1") (pinfunction "~{CS}_1") (pintype "bidirectional"))
      (node (ref "R18") (pin "1") (pinfunction "1_1") (pintype "passive"))
      (node (ref "R19") (pin "2") (pinfunction "2_2") (pintype "passive"))
    )
    (net (code "130") (name "~{RST}") (class "Default")
      (node (ref "IC1") (pin "37") (pinfunction "~{RSTN}_37") (pintype "input"))
      (node (ref "IC2") (pin "31") (pinfunction "GPIO20_31") (pintype "bidirectional"))
      (node (ref "R14") (pin "1") (pinfunction "1_1") (pintype "passive"))
    )
    (net (code "131") (name "~{SPI0_CS}") (class "Default")
      (node (ref "IC1") (pin "32") (pinfunction "~{SCSN}_32") (pintype "input"))
      (node (ref "IC2") (pin "28") (pinfunction "GPIO17_28") (pintype "bidirectional"))
    )
    (net (code "132") (name "~{SPI1_CS_S}") (class "Default")
      (node (ref "IC2") (pin "8") (pinfunction "GPIO6_8") (pintype "bidirectional"))
      (node (ref "J2") (pin "11") (pinfunction "11_11") (pintype "bidirectional"))
    )
    (net (code "133") (name "~{SPI1_CS}") (class "Default")
      (node (ref "IC2") (pin "12") (pinfunction "GPIO9_12") (pintype "bidirectional"))
      (node (ref "IC8") (pin "9") (pinfunction "~{CS}_9") (pintype "input"))
    )
  )
)
